# SCH_Amiga-KickSmash-32-in-system-flash_2.net
KiCad netlist of a schematic drawn in EasyEDA
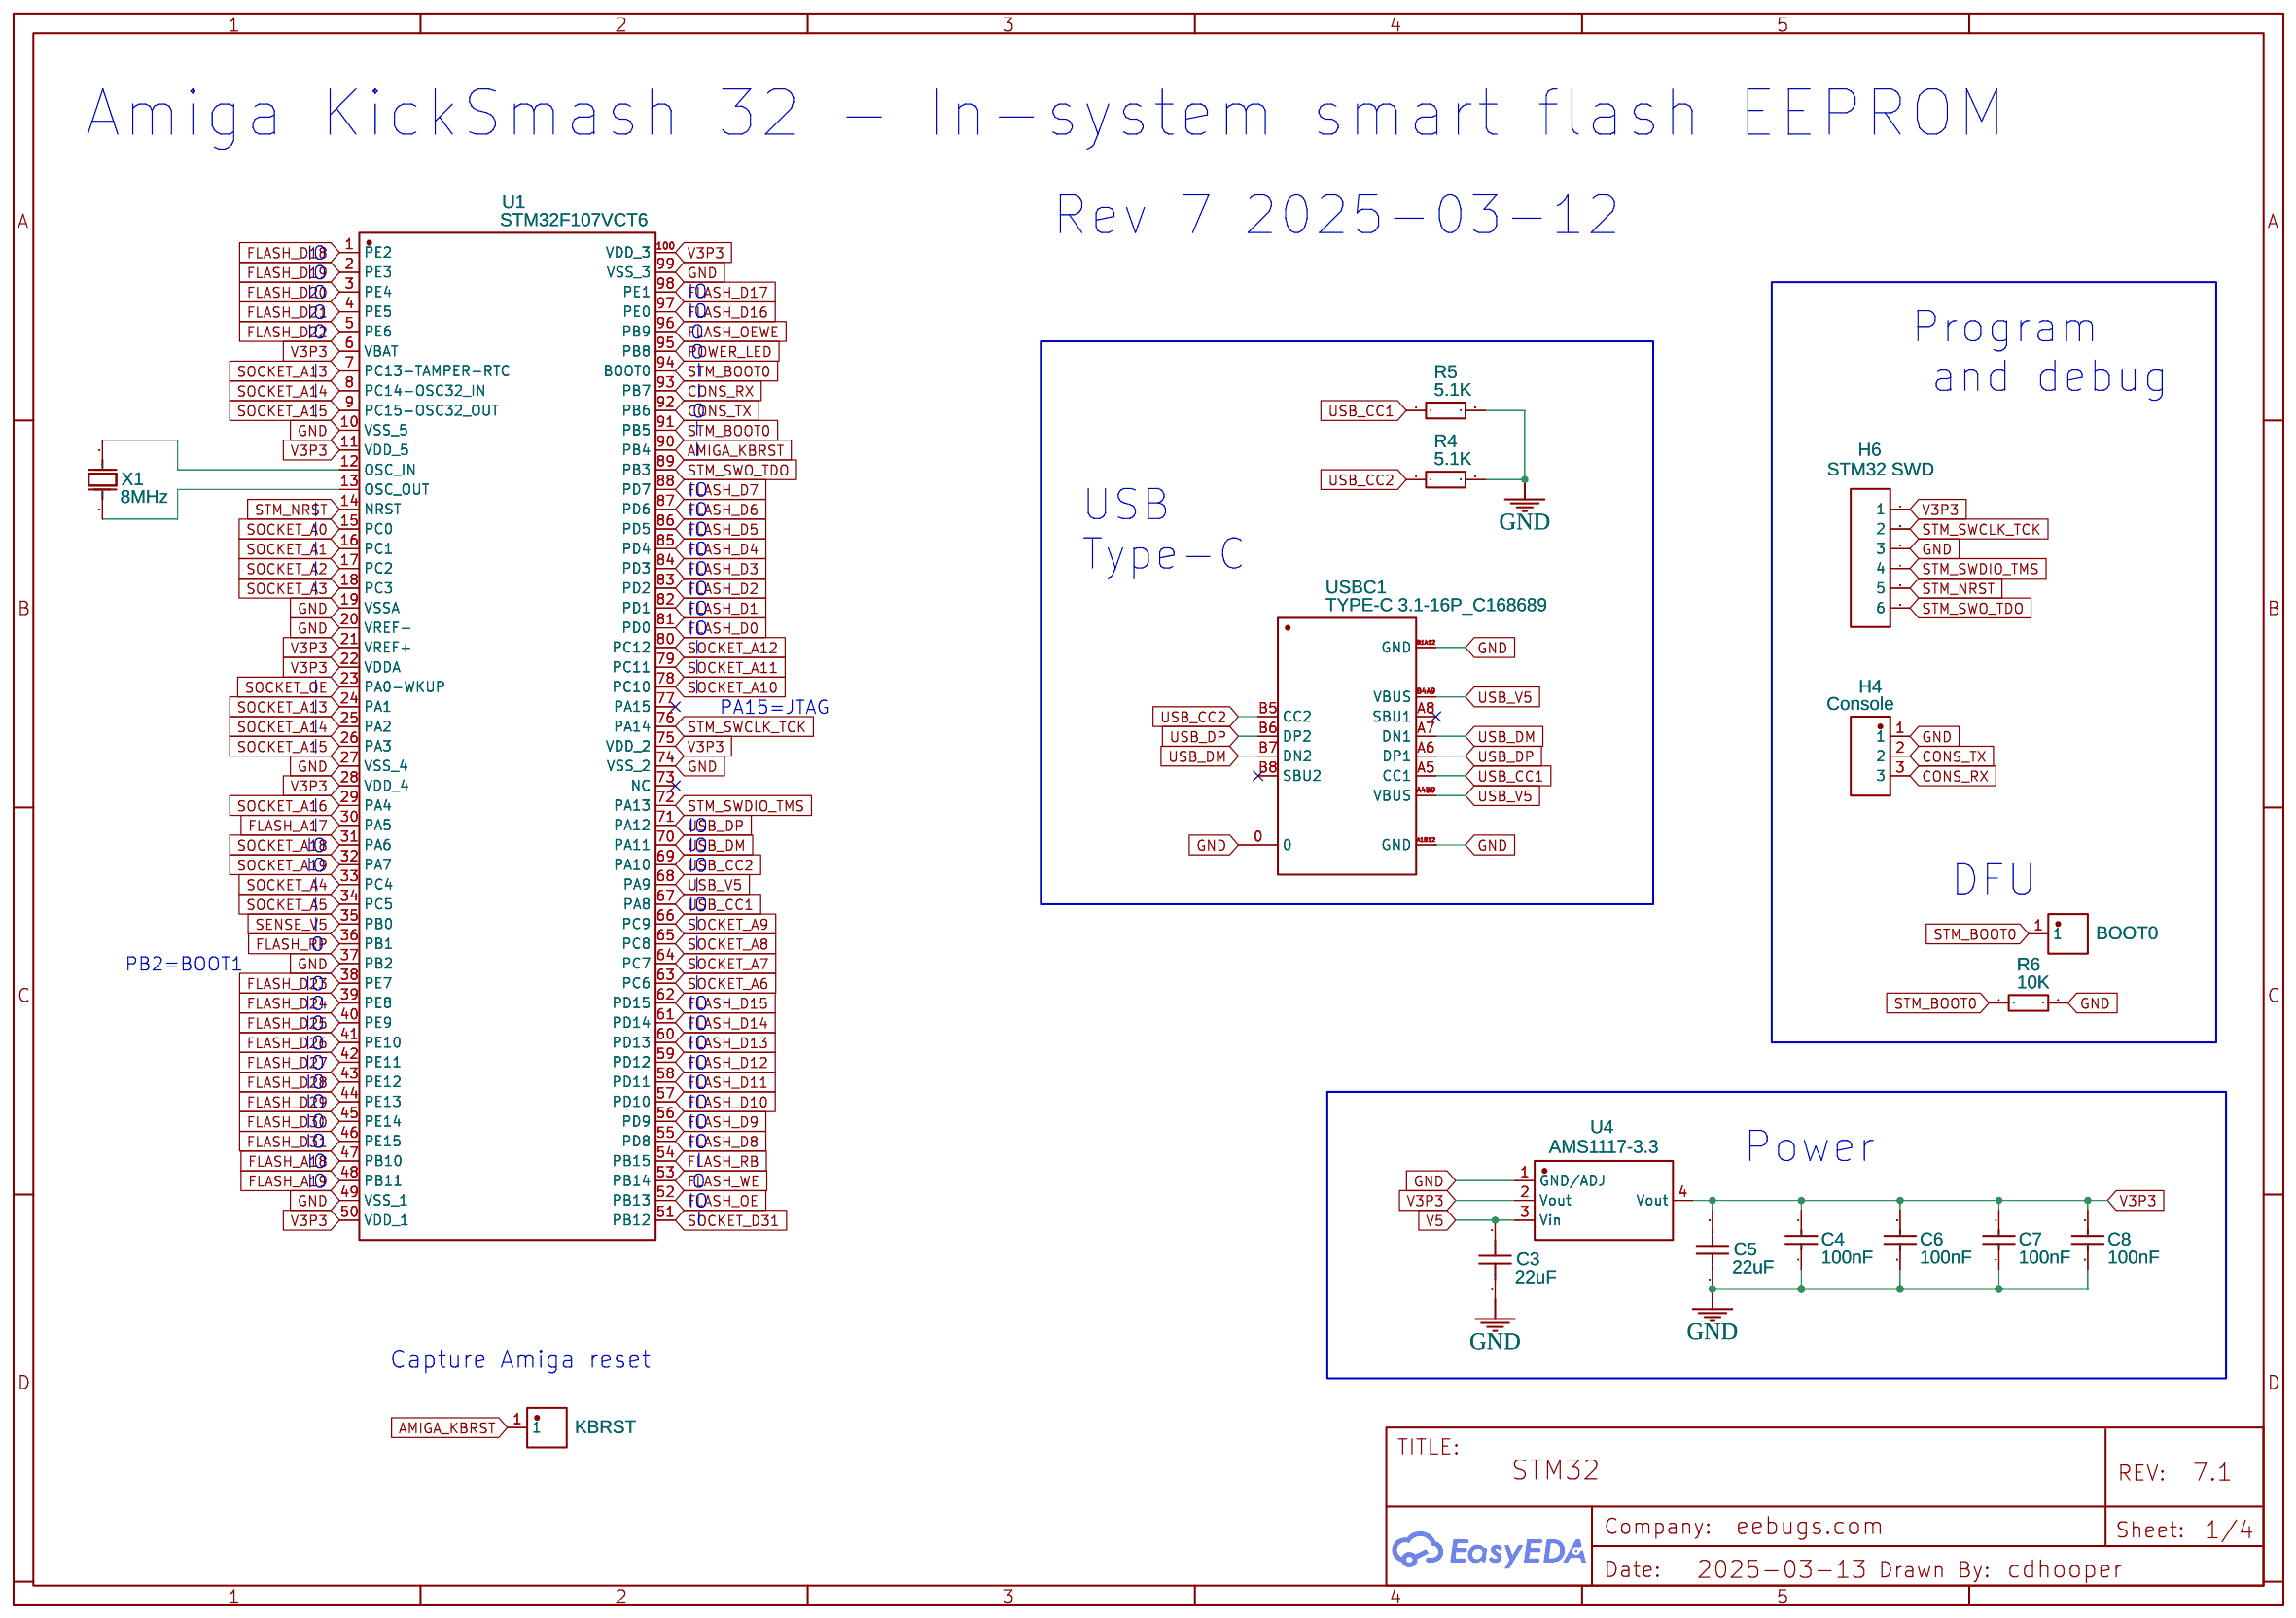
[diagram p0: STM32]
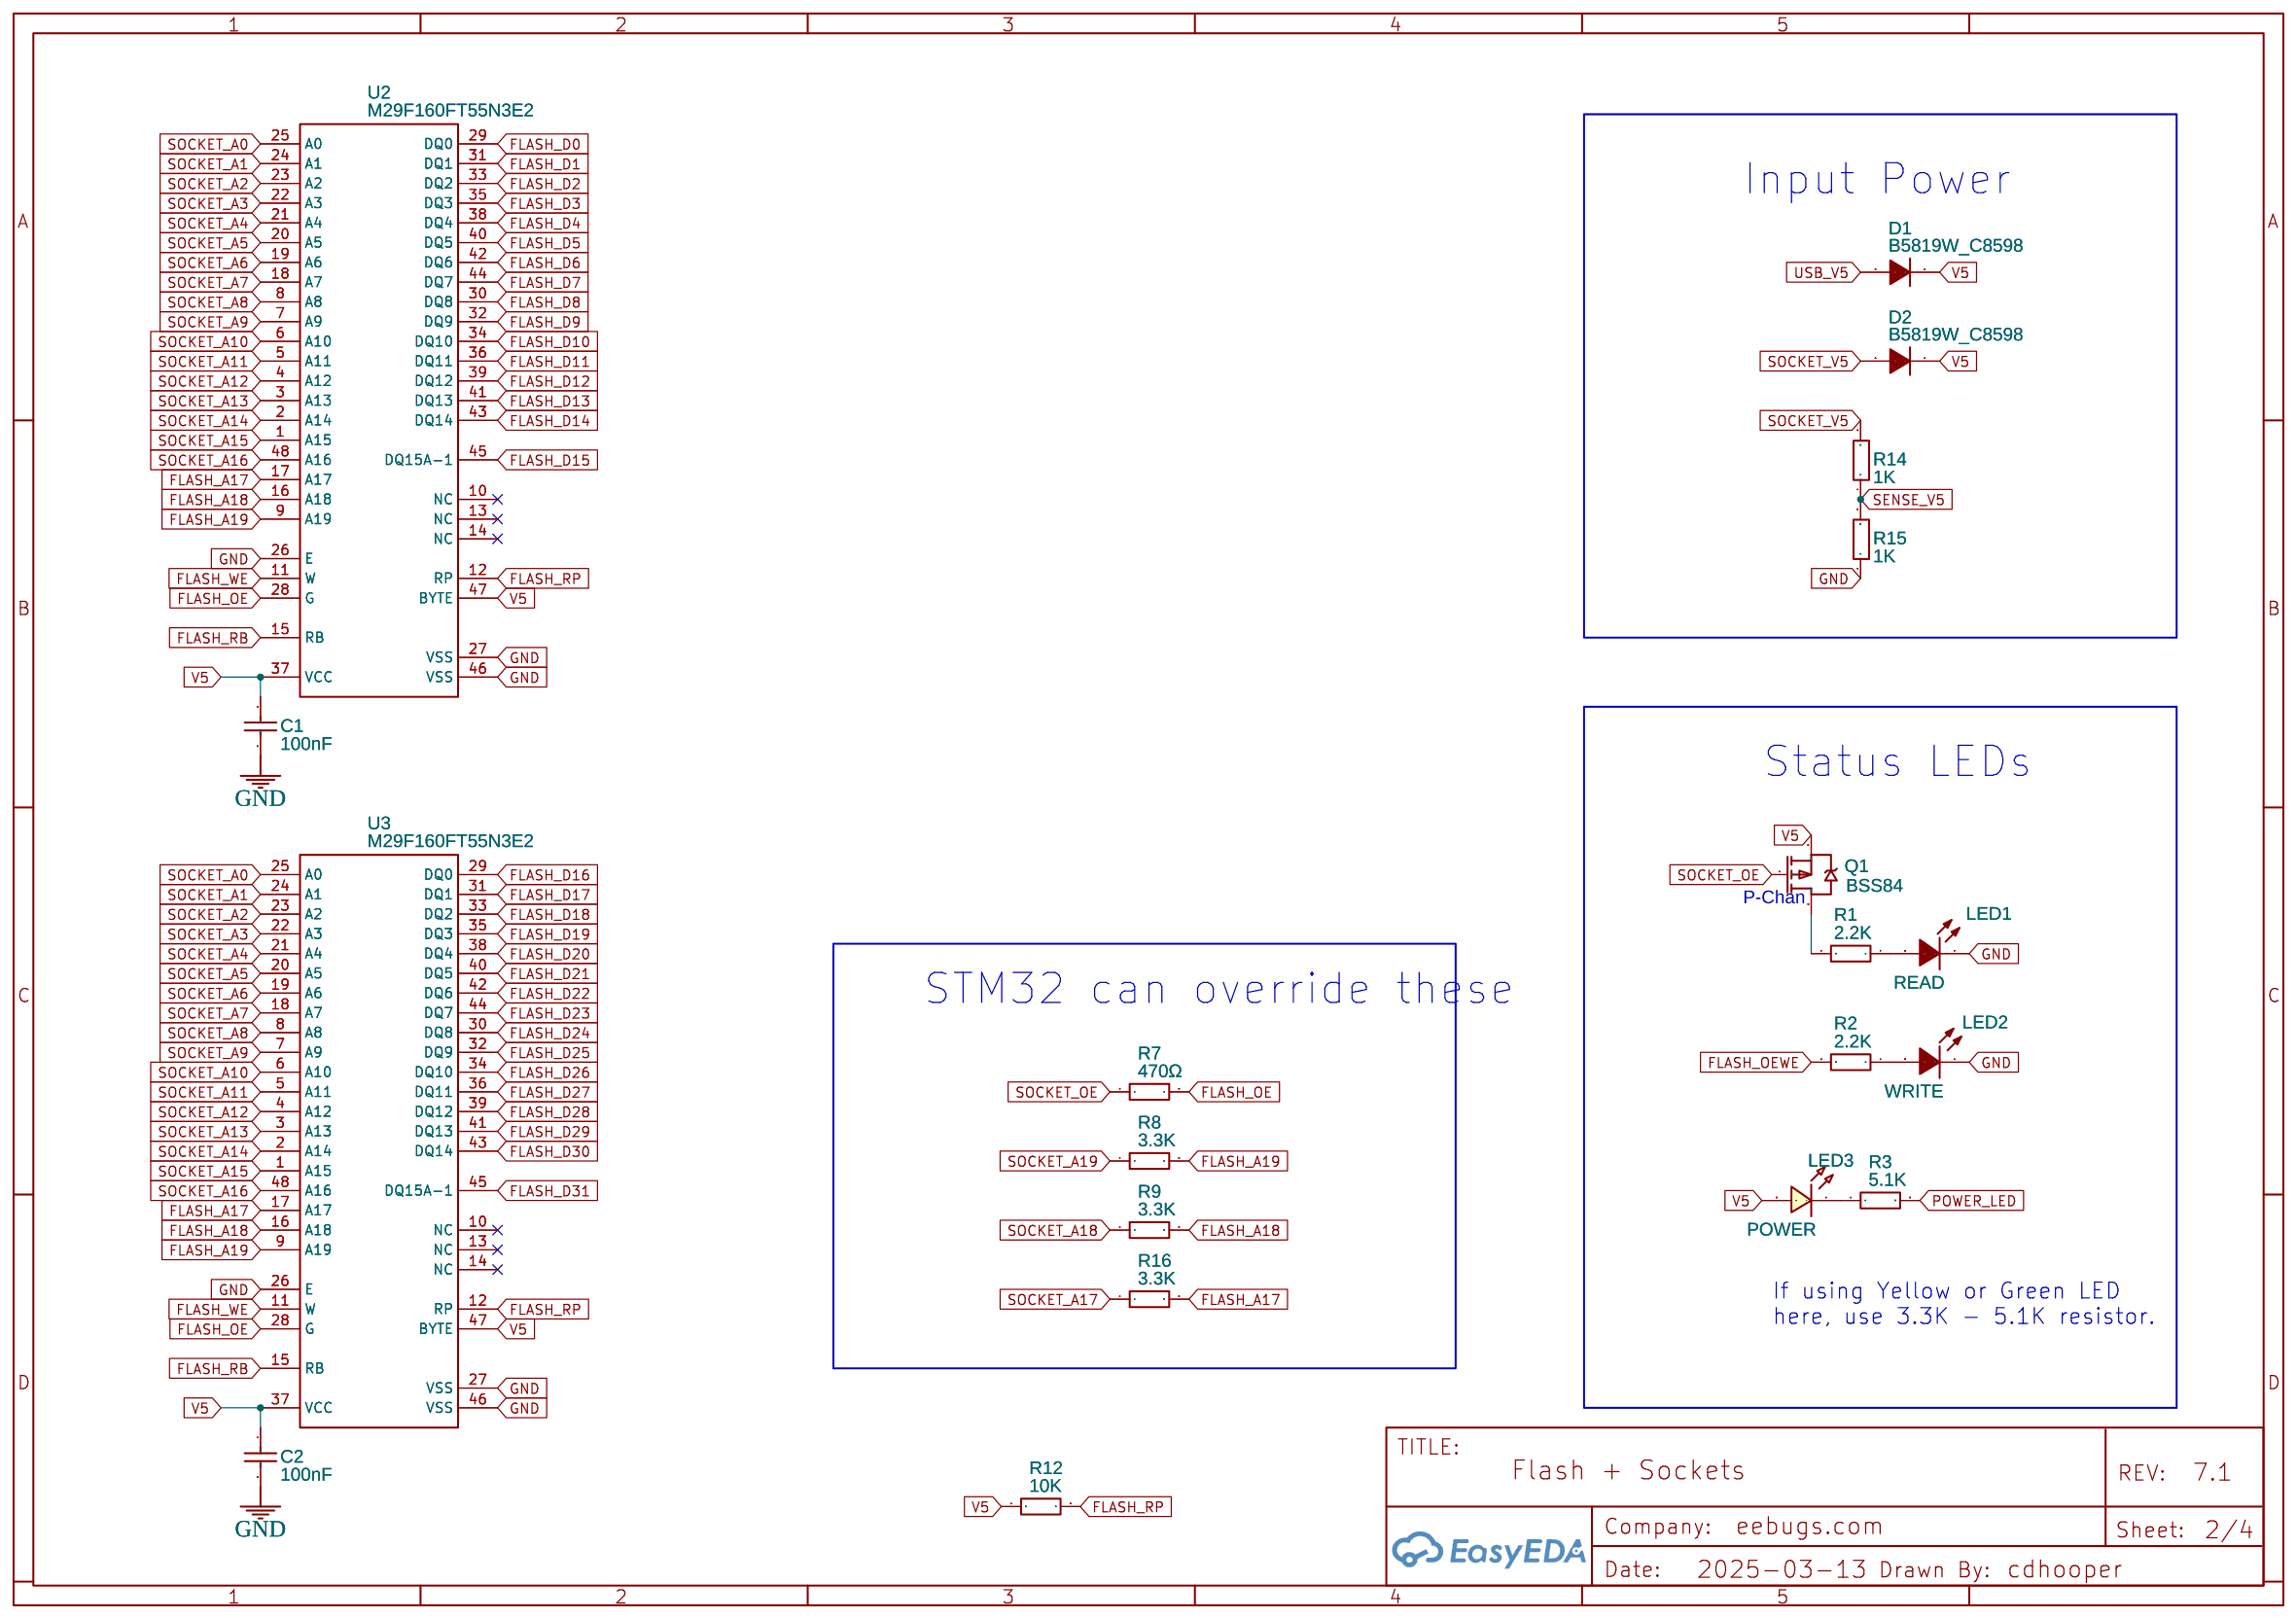
[diagram p1: Flash]
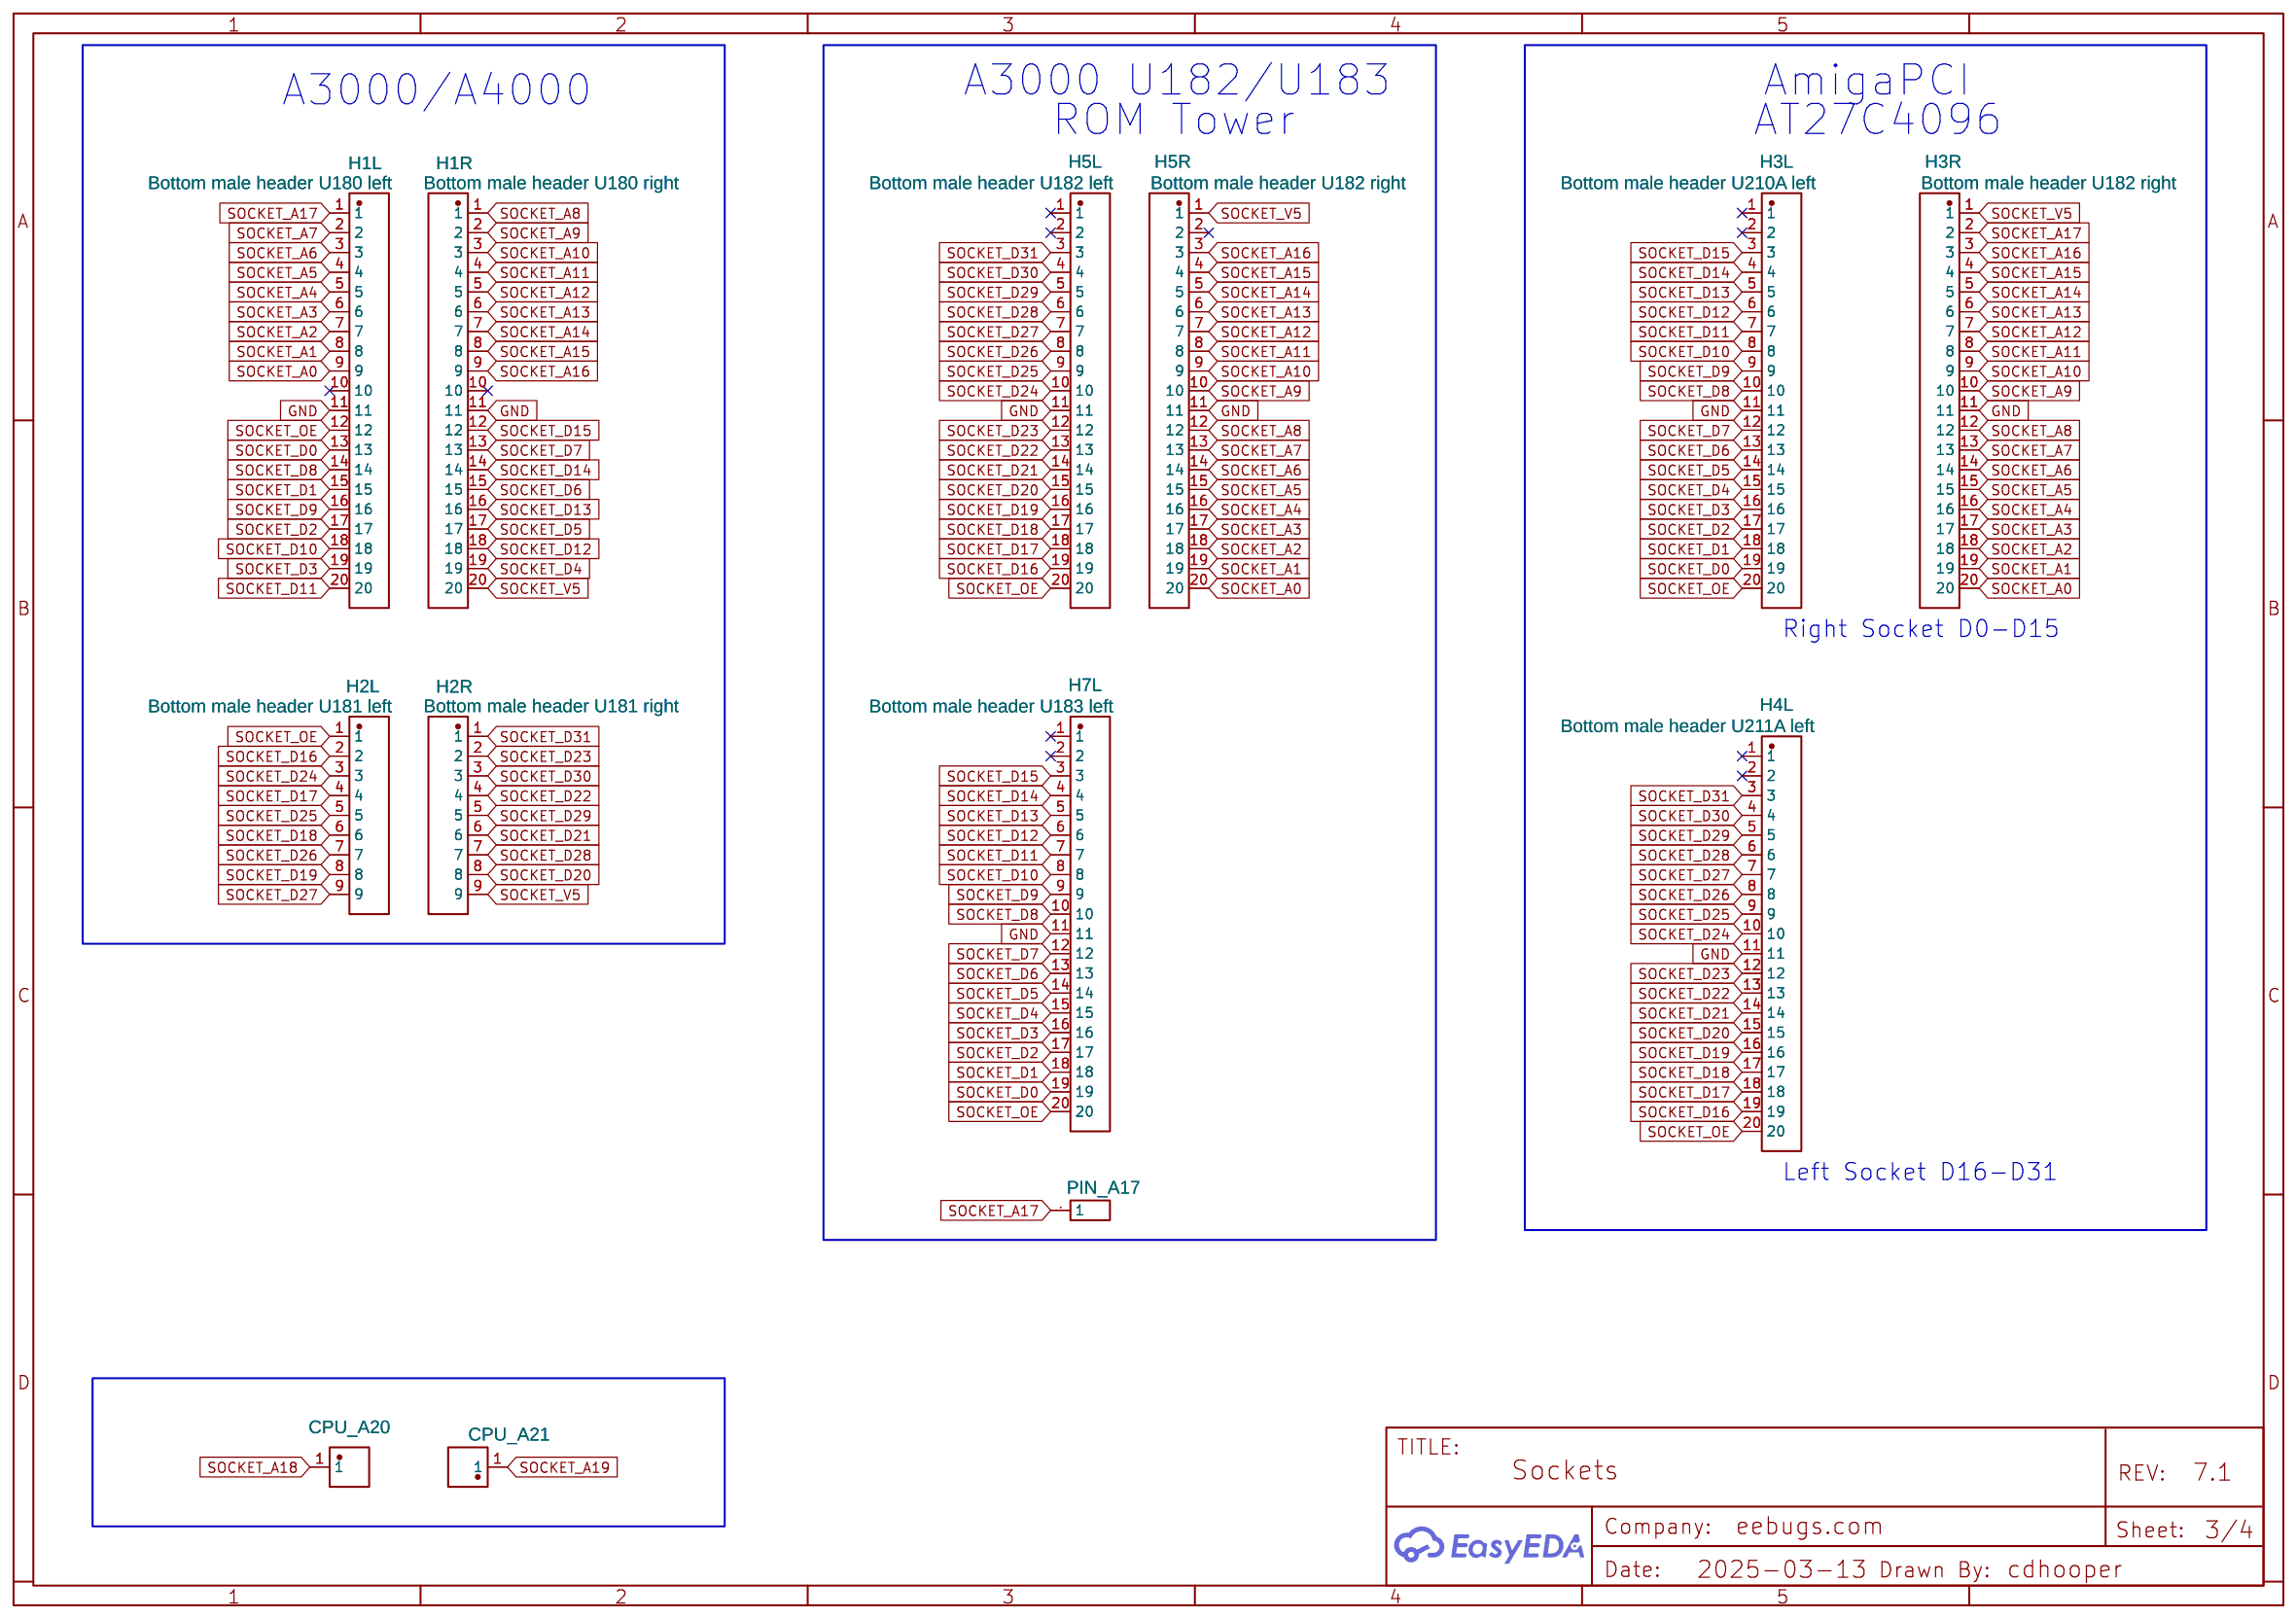
[diagram p2: Sockets]
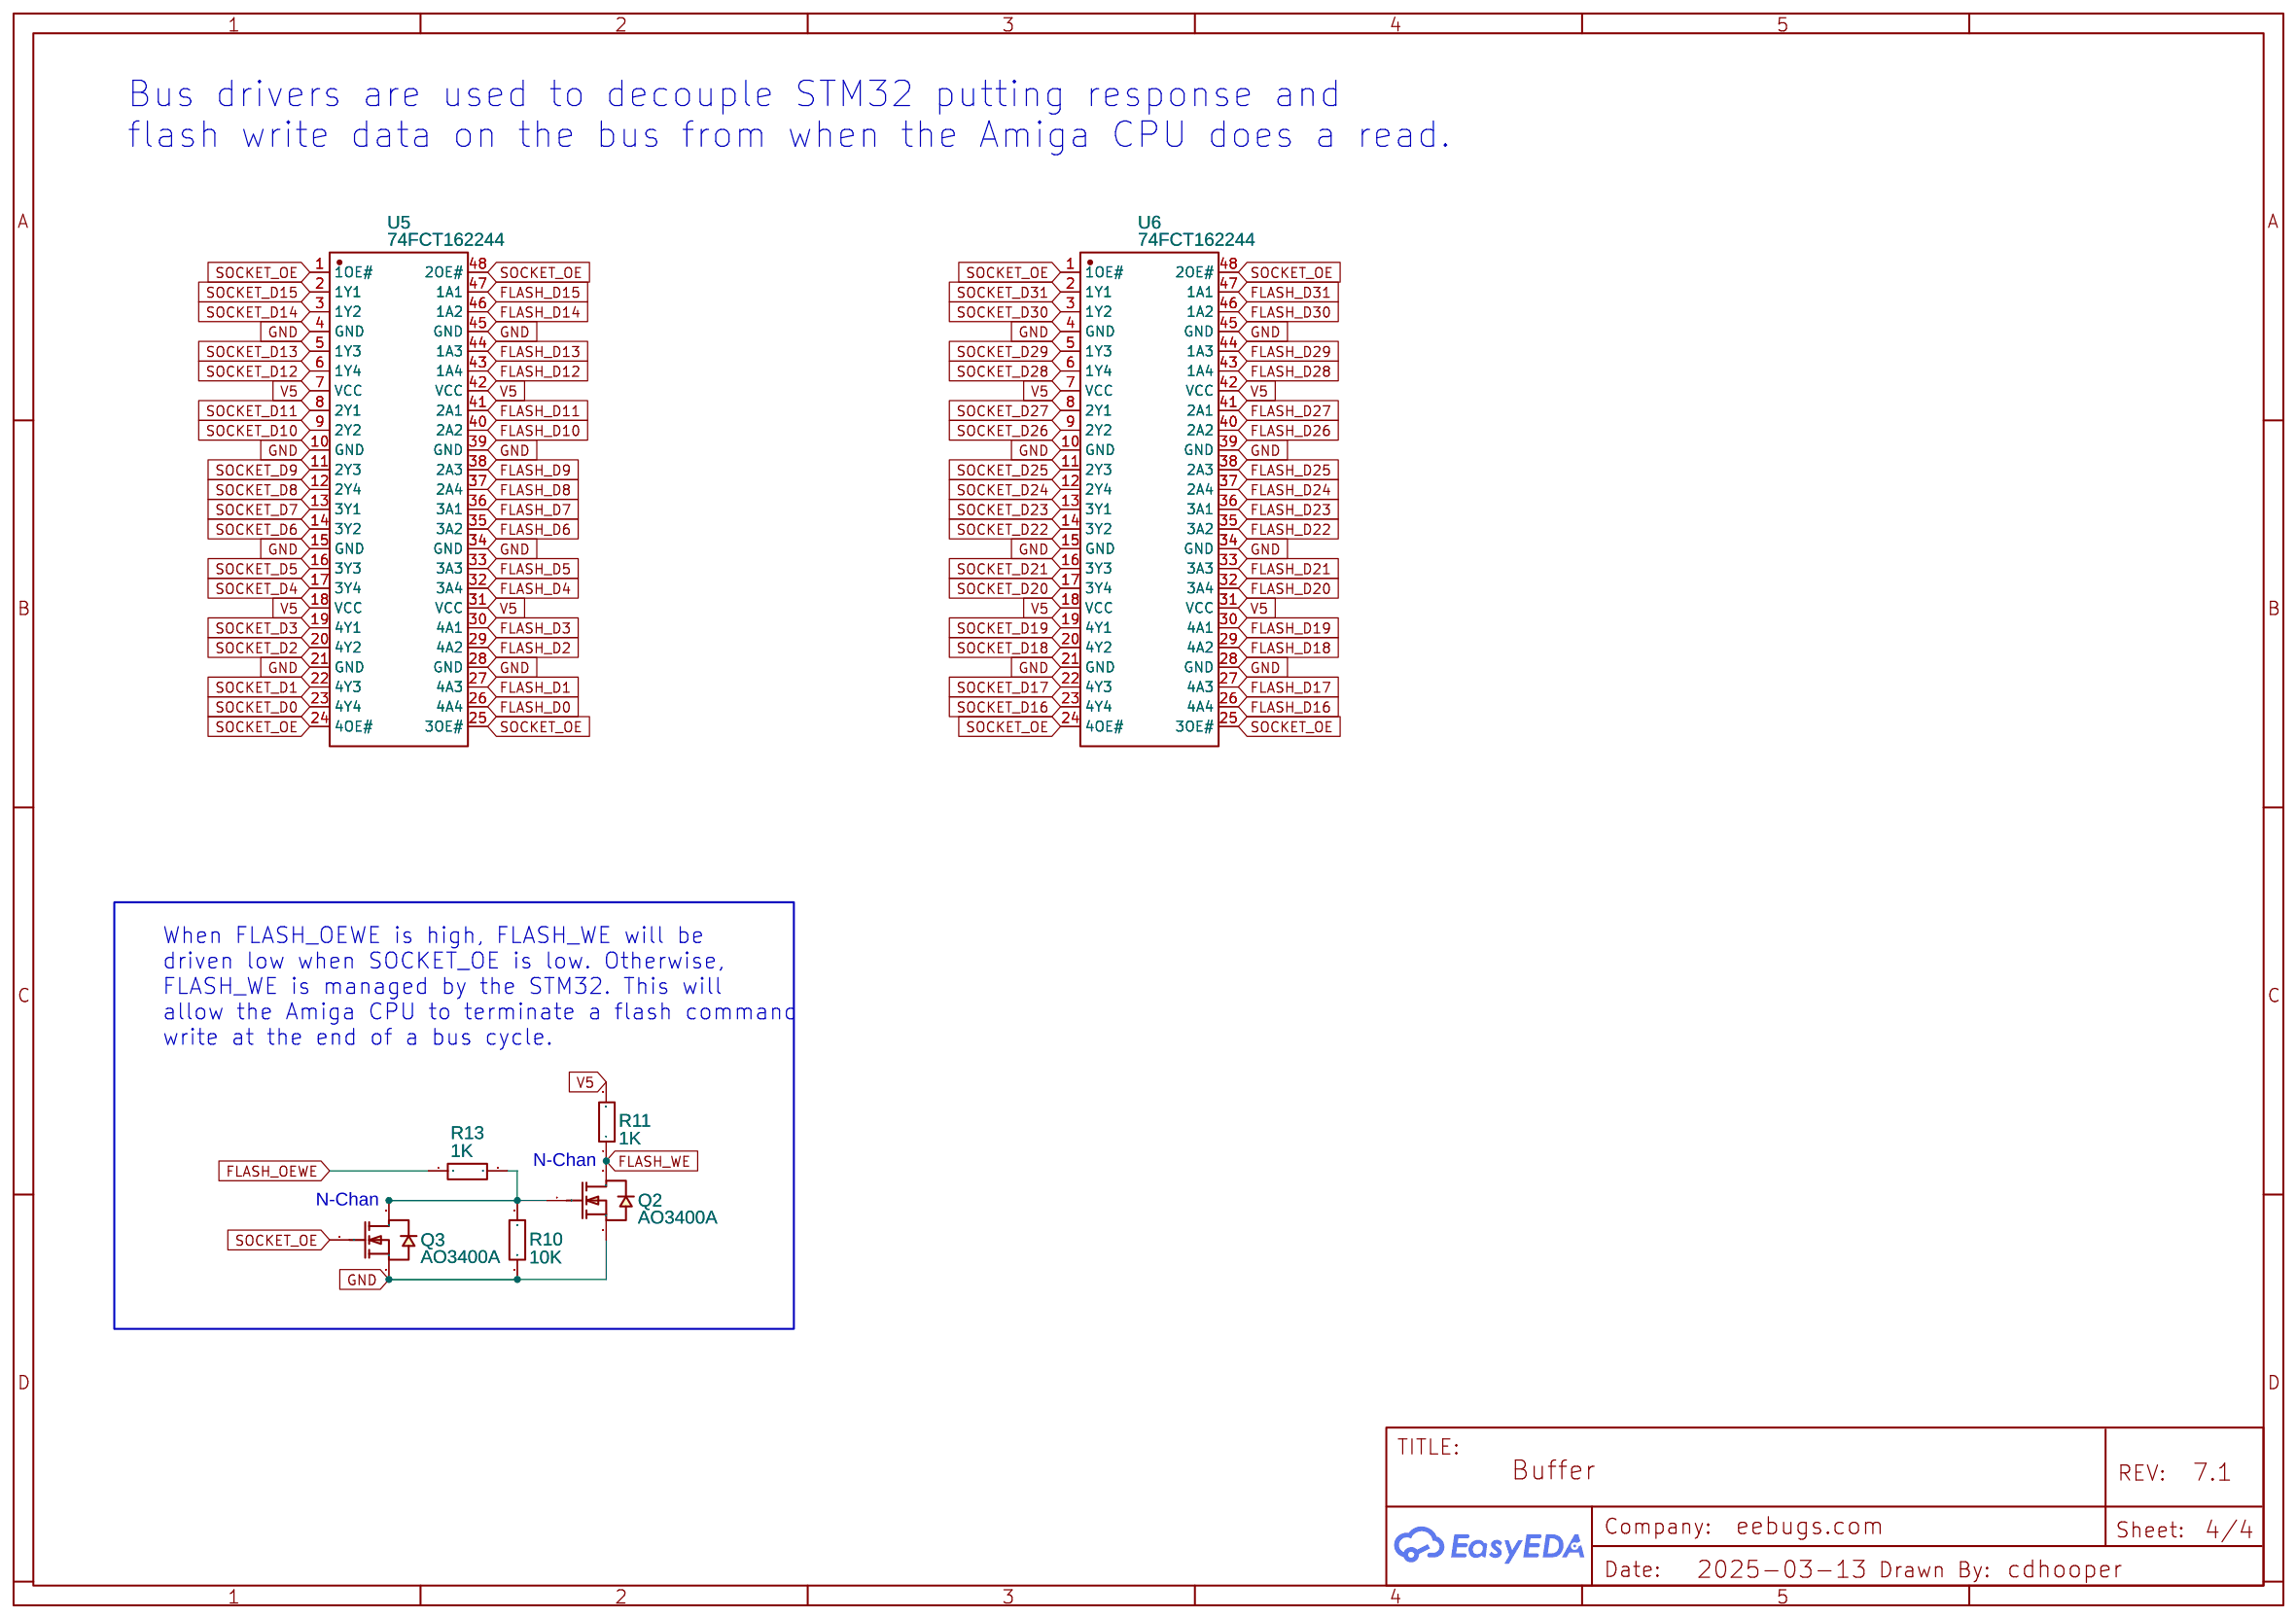
[diagram p3: Buffer]

(export (version "E")
  (design (tool "Eeschema 10.0.6"))
  (components
    (comp (ref "C3")
      (value "22uF")
      (fields (field (name "Manufacturer Part") "CL21A226MAQNNNE") (field (name "Manufacturer") "SAMSUNG"))
      (libsource (lib "") (part "CL21A226MAQNNNE"))
    )
    (comp (ref "C4")
      (value "100nF")
      (fields (field (name "Manufacturer Part") "CC0805KRX7R9BB104") (field (name "Manufacturer") "YAGEO"))
      (libsource (lib "") (part "CC0805KRX7R9BB104"))
    )
    (comp (ref "C5")
      (value "22uF")
      (fields (field (name "Manufacturer Part") "CL21A226MAQNNNE") (field (name "Manufacturer") "SAMSUNG"))
      (libsource (lib "") (part "CL21A226MAQNNNE"))
    )
    (comp (ref "C6")
      (value "100nF")
      (fields (field (name "Manufacturer Part") "CC0805KRX7R9BB104") (field (name "Manufacturer") "YAGEO"))
      (libsource (lib "") (part "CC0805KRX7R9BB104"))
    )
    (comp (ref "C7")
      (value "100nF")
      (fields (field (name "Manufacturer Part") "CC0805KRX7R9BB104") (field (name "Manufacturer") "YAGEO"))
      (libsource (lib "") (part "CC0805KRX7R9BB104"))
    )
    (comp (ref "C8")
      (value "100nF")
      (fields (field (name "Manufacturer Part") "CC0805KRX7R9BB104") (field (name "Manufacturer") "YAGEO"))
      (libsource (lib "") (part "CC0805KRX7R9BB104"))
    )
    (comp (ref "H3")
      (value "KBRST")
      (fields
        (field (name "Manufacturer Part") "X6511WR-01H-C60D30R2")
        (field (name "Manufacturer") "XKB Connection(中国星坤)")
      )
      (libsource (lib "") (part "X6511WR-01H-C30D60R2"))
    )
    (comp (ref "H4")
      (value "Console")
      (fields (field (name "Manufacturer Part") "PZ254R-11-03P") (field (name "Manufacturer") "XFCN(兴飞)"))
      (libsource (lib "") (part "PZ254R-11-03P"))
    )
    (comp (ref "H5")
      (value "BOOT0")
      (fields
        (field (name "Manufacturer Part") "X6511WR-01H-C60D30R2")
        (field (name "Manufacturer") "XKB Connection(中国星坤)")
      )
      (libsource (lib "") (part "X6511WR-01H-C30D60R2"))
    )
    (comp (ref "H6")
      (value "STM32 SWD")
      (fields (field (name "Manufacturer Part") "Female header 1*6p") (field (name "Manufacturer") "BOOMELE"))
      (libsource (lib "") (part "Unknown_945_-530"))
    )
    (comp (ref "R4")
      (value "5.1K")
      (fields (field (name "Manufacturer Part") "0805W8F5101T5E") (field (name "Manufacturer") "UniOhm"))
      (libsource (lib "") (part "0805W8F5101T5E"))
    )
    (comp (ref "R5")
      (value "5.1K")
      (fields (field (name "Manufacturer Part") "0805W8F5101T5E") (field (name "Manufacturer") "UniOhm"))
      (libsource (lib "") (part "0805W8F5101T5E"))
    )
    (comp (ref "R6")
      (value "10K")
      (fields (field (name "Manufacturer Part") "0805W8F1002T5E") (field (name "Manufacturer") "UniOhm"))
      (libsource (lib "") (part "0805W8F1002T5E"))
    )
    (comp (ref "U1")
      (value "STM32F107VCT6")
      (fields (field (name "Manufacturer") "STMicroelectronics"))
      (libsource (lib "") (part "STM32F107VCT6"))
    )
    (comp (ref "U4")
      (value "AMS1117-3.3")
      (fields (field (name "Manufacturer") "AMS"))
      (libsource (lib "") (part "AMS1117-3.3"))
    )
    (comp (ref "USBC1")
      (value "TYPE-C 3.1-16P_C168689")
      (fields (field (name "Manufacturer") "LCSC"))
      (libsource (lib "") (part "TYPE-C 3.1-16P_C168689"))
    )
    (comp (ref "X1")
      (value "8MHz")
      (fields (field (name "Manufacturer Part") "X50328MSB2GI") (field (name "Manufacturer") "YXC"))
      (libsource (lib "") (part "X50328MSB2GI"))
    )
    (comp (ref "C1")
      (value "100nF")
      (fields (field (name "Manufacturer Part") "CC0805KRX7R9BB104") (field (name "Manufacturer") "YAGEO"))
      (libsource (lib "") (part "CC0805KRX7R9BB104"))
    )
    (comp (ref "C2")
      (value "100nF")
      (fields (field (name "Manufacturer Part") "CC0805KRX7R9BB104") (field (name "Manufacturer") "YAGEO"))
      (libsource (lib "") (part "CC0805KRX7R9BB104"))
    )
    (comp (ref "D1")
      (value "B5819W_C8598")
      (fields (field (name "Manufacturer Part") "B5819W") (field (name "Manufacturer") "CJ"))
      (libsource (lib "") (part "B5819W_C8598"))
    )
    (comp (ref "D2")
      (value "B5819W_C8598")
      (fields (field (name "Manufacturer Part") "B5819W") (field (name "Manufacturer") "CJ"))
      (libsource (lib "") (part "B5819W_C8598"))
    )
    (comp (ref "LED1")
      (value "READ")
      (fields (field (name "Manufacturer Part") "17-21SUYC/TR8") (field (name "Manufacturer") "KENTO"))
      (libsource (lib "") (part "17-21SUYC/TR8"))
    )
    (comp (ref "LED2")
      (value "WRITE")
      (fields (field (name "Manufacturer Part") "0805G (Green)") (field (name "Manufacturer") "KENTO"))
      (libsource (lib "") (part "0805G (Green)"))
    )
    (comp (ref "LED3")
      (value "POWER")
      (fields
        (field (name "Manufacturer Part") "P2-0805UVTCS2-0.8T")
        (field (name "Manufacturer") "TUOZHAN(拓展光电)")
      )
      (libsource (lib "") (part "P2-0805UVTCS2-0.8T"))
    )
    (comp (ref "Q1")
      (value "BSS84")
      (fields (field (name "Manufacturer Part") "LBSS84LT1G") (field (name "Manufacturer") "LRC"))
      (libsource (lib "") (part "Unknown_905_-370"))
    )
    (comp (ref "R1")
      (value "2.2K")
      (fields (field (name "Manufacturer Part") "0805W8F2201T5E") (field (name "Manufacturer") "UniOhm"))
      (libsource (lib "") (part "0805W8F2201T5E"))
    )
    (comp (ref "R2")
      (value "2.2K")
      (fields (field (name "Manufacturer Part") "0805W8F2201T5E") (field (name "Manufacturer") "UniOhm"))
      (libsource (lib "") (part "0805W8F2201T5E"))
    )
    (comp (ref "R3")
      (value "5.1K")
      (fields (field (name "Manufacturer Part") "0805W8F5101T5E") (field (name "Manufacturer") "UniOhm"))
      (libsource (lib "") (part "0805W8F5101T5E"))
    )
    (comp (ref "R7")
      (value "470Ω")
      (fields
        (field (name "Manufacturer Part") "0805W8F4700T5E")
        (field (name "Manufacturer") "UNI-ROYAL(厚声)")
      )
      (libsource (lib "") (part "0805W8F4700T5E"))
    )
    (comp (ref "R8")
      (value "3.3K")
      (fields
        (field (name "Manufacturer Part") "0805W8F3301T5E")
        (field (name "Manufacturer") "UNI-ROYAL(厚声)")
      )
      (libsource (lib "") (part "0805W8F3301T5E"))
    )
    (comp (ref "R9")
      (value "3.3K")
      (fields
        (field (name "Manufacturer Part") "0805W8F3301T5E")
        (field (name "Manufacturer") "UNI-ROYAL(厚声)")
      )
      (libsource (lib "") (part "0805W8F3301T5E"))
    )
    (comp (ref "R12")
      (value "10K")
      (fields (field (name "Manufacturer Part") "0805W8F1002T5E") (field (name "Manufacturer") "UniOhm"))
      (libsource (lib "") (part "0805W8F1002T5E"))
    )
    (comp (ref "R14")
      (value "1K")
      (fields (field (name "Manufacturer Part") "0805W8F1001T5E") (field (name "Manufacturer") "UniOhm"))
      (libsource (lib "") (part "0805W8F1001T5E"))
    )
    (comp (ref "R15")
      (value "1K")
      (fields (field (name "Manufacturer Part") "0805W8F1001T5E") (field (name "Manufacturer") "UniOhm"))
      (libsource (lib "") (part "0805W8F1001T5E"))
    )
    (comp (ref "R16")
      (value "3.3K")
      (fields
        (field (name "Manufacturer Part") "0805W8F3301T5E")
        (field (name "Manufacturer") "UNI-ROYAL(厚声)")
      )
      (libsource (lib "") (part "0805W8F3301T5E"))
    )
    (comp (ref "U2") (value "M29F160FT55N3E2") (libsource (lib "") (part "M29F160FT55N3E2")))
    (comp (ref "U3") (value "M29F160FT55N3E2") (libsource (lib "") (part "M29F160FT55N3E2")))
    (comp (ref "H1L")
      (value "Bottom male header U180 left")
      (fields (field (name "Manufacturer Part") "PZ254-1-20-Z-C") (field (name "Manufacturer") "HCTL(华灿天禄)"))
      (libsource (lib "") (part "PZ254-1-20-Z-C"))
    )
    (comp (ref "H1R")
      (value "Bottom male header U180 right")
      (fields (field (name "Manufacturer Part") "PZ254-1-20-Z-C") (field (name "Manufacturer") "HCTL(华灿天禄)"))
      (libsource (lib "") (part "PZ254-1-20-Z-C_1"))
    )
    (comp (ref "H2L")
      (value "Bottom male header U181 left")
      (fields (field (name "Manufacturer Part") "PZ254-1-09-Z-C") (field (name "Manufacturer") "HCTL(华灿天禄)"))
      (libsource (lib "") (part "PZ254-1-09-Z-C_1"))
    )
    (comp (ref "H2R")
      (value "Bottom male header U181 right")
      (fields (field (name "Manufacturer Part") "PZ254-1-09-Z-C") (field (name "Manufacturer") "HCTL(华灿天禄)"))
      (libsource (lib "") (part "PZ254-1-09-Z-C"))
    )
    (comp (ref "H3L")
      (value "Bottom male header U210A left")
      (fields (field (name "Manufacturer Part") "2.54mm 1*20PHeader") (field (name "Manufacturer") "BOOMELE"))
      (libsource (lib "") (part "Header-Male-2.54_1x20_3"))
    )
    (comp (ref "H3R")
      (value "Bottom male header U182 right")
      (fields (field (name "Manufacturer Part") "2.54mm 1*20PHeader") (field (name "Manufacturer") "BOOMELE"))
      (libsource (lib "") (part "Header-Male-2.54_1x20_2"))
    )
    (comp (ref "H4L")
      (value "Bottom male header U211A left")
      (fields (field (name "Manufacturer Part") "2.54mm 1*20PHeader") (field (name "Manufacturer") "BOOMELE"))
      (libsource (lib "") (part "Header-Male-2.54_1x20_5"))
    )
    (comp (ref "H5L")
      (value "Bottom male header U182 left")
      (fields (field (name "Manufacturer Part") "2.54mm 1*20PHeader") (field (name "Manufacturer") "BOOMELE"))
      (libsource (lib "") (part "Header-Male-2.54_1x20_1"))
    )
    (comp (ref "H5R")
      (value "Bottom male header U182 right")
      (fields (field (name "Manufacturer Part") "2.54mm 1*20PHeader") (field (name "Manufacturer") "BOOMELE"))
      (libsource (lib "") (part "Header-Male-2.54_1x20"))
    )
    (comp (ref "H7")
      (value "CPU_A20")
      (fields
        (field (name "Manufacturer Part") "X6511WR-01H-C60D30R2")
        (field (name "Manufacturer") "XKB Connection(中国星坤)")
      )
      (libsource (lib "") (part "X6511WR-01H-C30D60R2_1"))
    )
    (comp (ref "H7L")
      (value "Bottom male header U183 left")
      (fields (field (name "Manufacturer Part") "2.54mm 1*20PHeader") (field (name "Manufacturer") "BOOMELE"))
      (libsource (lib "") (part "Header-Male-2.54_1x20_4"))
    )
    (comp (ref "H8")
      (value "CPU_A21")
      (fields
        (field (name "Manufacturer Part") "X6511WR-01H-C60D30R2")
        (field (name "Manufacturer") "XKB Connection(中国星坤)")
      )
      (libsource (lib "") (part "X6511WR-01H-C30D60R2"))
    )
    (comp (ref "H9")
      (value "PIN_A17")
      (fields
        (field (name "Manufacturer Part") "Header-Male-2.54_1x1")
        (field (name "Manufacturer") "ReliaPro")
      )
      (libsource (lib "") (part "Header-Male-2.54_1x1"))
    )
    (comp (ref "Q2")
      (value "AO3400A")
      (fields (field (name "Manufacturer") "AOS"))
      (libsource (lib "") (part "AO3400A"))
    )
    (comp (ref "Q3")
      (value "AO3400A")
      (fields (field (name "Manufacturer") "AOS"))
      (libsource (lib "") (part "AO3400A"))
    )
    (comp (ref "R10")
      (value "10K")
      (fields (field (name "Manufacturer Part") "0805W8F1002T5E") (field (name "Manufacturer") "UniOhm"))
      (libsource (lib "") (part "0805W8F1002T5E"))
    )
    (comp (ref "R11")
      (value "1K")
      (fields (field (name "Manufacturer Part") "0805W8F1001T5E") (field (name "Manufacturer") "UniOhm"))
      (libsource (lib "") (part "0805W8F1001T5E"))
    )
    (comp (ref "R13")
      (value "1K")
      (fields (field (name "Manufacturer Part") "0805W8F1001T5E") (field (name "Manufacturer") "UniOhm"))
      (libsource (lib "") (part "0805W8F1001T5E_1"))
    )
    (comp (ref "U5")
      (value "74FCT162244")
      (fields
        (field (name "Manufacturer Part") "74FCT162244CTPAG")
        (field (name "Manufacturer") "RENESAS(瑞萨)/IDT")
      )
      (libsource (lib "") (part "74FCT162244CTPAG"))
    )
    (comp (ref "U6")
      (value "74FCT162244")
      (fields
        (field (name "Manufacturer Part") "74FCT162244CTPAG")
        (field (name "Manufacturer") "RENESAS(瑞萨)/IDT")
      )
      (libsource (lib "") (part "74FCT162244CTPAG"))
    )
  )
  (nets
    (net (code "1") (name "AMIGA_KBRST") (class "Default")
      (node (ref "H3") (pin "1") (pinfunction "1_1") (pintype "unspecified"))
      (node (ref "U1") (pin "90") (pinfunction "PB4_90") (pintype "unspecified"))
    )
    (net (code "2") (name "CONS_RX") (class "Default")
      (node (ref "H4") (pin "3") (pinfunction "3_3") (pintype "unspecified"))
      (node (ref "U1") (pin "93") (pinfunction "PB7_93") (pintype "unspecified"))
    )
    (net (code "3") (name "CONS_TX") (class "Default")
      (node (ref "H4") (pin "2") (pinfunction "2_2") (pintype "unspecified"))
      (node (ref "U1") (pin "92") (pinfunction "PB6_92") (pintype "unspecified"))
    )
    (net (code "4") (name "FLASH_A17") (class "Default")
      (node (ref "R16") (pin "2") (pinfunction "2_2") (pintype "input"))
      (node (ref "U1") (pin "30") (pinfunction "PA5_30") (pintype "unspecified"))
      (node (ref "U2") (pin "17") (pinfunction "A17_17") (pintype "unspecified"))
      (node (ref "U3") (pin "17") (pinfunction "A17_17") (pintype "unspecified"))
    )
    (net (code "5") (name "FLASH_A18") (class "Default")
      (node (ref "R9") (pin "2") (pinfunction "2_2") (pintype "input"))
      (node (ref "U1") (pin "47") (pinfunction "PB10_47") (pintype "unspecified"))
      (node (ref "U2") (pin "16") (pinfunction "A18_16") (pintype "unspecified"))
      (node (ref "U3") (pin "16") (pinfunction "A18_16") (pintype "unspecified"))
    )
    (net (code "6") (name "FLASH_A19") (class "Default")
      (node (ref "R8") (pin "2") (pinfunction "2_2") (pintype "input"))
      (node (ref "U1") (pin "48") (pinfunction "PB11_48") (pintype "unspecified"))
      (node (ref "U2") (pin "9") (pinfunction "A19_9") (pintype "unspecified"))
      (node (ref "U3") (pin "9") (pinfunction "A19_9") (pintype "unspecified"))
    )
    (net (code "7") (name "FLASH_D0") (class "Default")
      (node (ref "U1") (pin "81") (pinfunction "PD0_81") (pintype "unspecified"))
      (node (ref "U2") (pin "29") (pinfunction "DQ0_29") (pintype "bidirectional"))
      (node (ref "U5") (pin "26") (pinfunction "4A4_26") (pintype "unspecified"))
    )
    (net (code "8") (name "FLASH_D1") (class "Default")
      (node (ref "U1") (pin "82") (pinfunction "PD1_82") (pintype "unspecified"))
      (node (ref "U2") (pin "31") (pinfunction "DQ1_31") (pintype "bidirectional"))
      (node (ref "U5") (pin "27") (pinfunction "4A3_27") (pintype "unspecified"))
    )
    (net (code "9") (name "FLASH_D2") (class "Default")
      (node (ref "U1") (pin "83") (pinfunction "PD2_83") (pintype "unspecified"))
      (node (ref "U2") (pin "33") (pinfunction "DQ2_33") (pintype "bidirectional"))
      (node (ref "U5") (pin "29") (pinfunction "4A2_29") (pintype "unspecified"))
    )
    (net (code "10") (name "FLASH_D3") (class "Default")
      (node (ref "U1") (pin "84") (pinfunction "PD3_84") (pintype "unspecified"))
      (node (ref "U2") (pin "35") (pinfunction "DQ3_35") (pintype "bidirectional"))
      (node (ref "U5") (pin "30") (pinfunction "4A1_30") (pintype "unspecified"))
    )
    (net (code "11") (name "FLASH_D4") (class "Default")
      (node (ref "U1") (pin "85") (pinfunction "PD4_85") (pintype "unspecified"))
      (node (ref "U2") (pin "38") (pinfunction "DQ4_38") (pintype "bidirectional"))
      (node (ref "U5") (pin "32") (pinfunction "3A4_32") (pintype "unspecified"))
    )
    (net (code "12") (name "FLASH_D5") (class "Default")
      (node (ref "U1") (pin "86") (pinfunction "PD5_86") (pintype "unspecified"))
      (node (ref "U2") (pin "40") (pinfunction "DQ5_40") (pintype "bidirectional"))
      (node (ref "U5") (pin "33") (pinfunction "3A3_33") (pintype "unspecified"))
    )
    (net (code "13") (name "FLASH_D6") (class "Default")
      (node (ref "U1") (pin "87") (pinfunction "PD6_87") (pintype "unspecified"))
      (node (ref "U2") (pin "42") (pinfunction "DQ6_42") (pintype "bidirectional"))
      (node (ref "U5") (pin "35") (pinfunction "3A2_35") (pintype "unspecified"))
    )
    (net (code "14") (name "FLASH_D7") (class "Default")
      (node (ref "U1") (pin "88") (pinfunction "PD7_88") (pintype "unspecified"))
      (node (ref "U2") (pin "44") (pinfunction "DQ7_44") (pintype "bidirectional"))
      (node (ref "U5") (pin "36") (pinfunction "3A1_36") (pintype "unspecified"))
    )
    (net (code "15") (name "FLASH_D8") (class "Default")
      (node (ref "U1") (pin "55") (pinfunction "PD8_55") (pintype "unspecified"))
      (node (ref "U2") (pin "30") (pinfunction "DQ8_30") (pintype "bidirectional"))
      (node (ref "U5") (pin "37") (pinfunction "2A4_37") (pintype "unspecified"))
    )
    (net (code "16") (name "FLASH_D9") (class "Default")
      (node (ref "U1") (pin "56") (pinfunction "PD9_56") (pintype "unspecified"))
      (node (ref "U2") (pin "32") (pinfunction "DQ9_32") (pintype "bidirectional"))
      (node (ref "U5") (pin "38") (pinfunction "2A3_38") (pintype "unspecified"))
    )
    (net (code "17") (name "FLASH_D10") (class "Default")
      (node (ref "U1") (pin "57") (pinfunction "PD10_57") (pintype "unspecified"))
      (node (ref "U2") (pin "34") (pinfunction "DQ10_34") (pintype "bidirectional"))
      (node (ref "U5") (pin "40") (pinfunction "2A2_40") (pintype "unspecified"))
    )
    (net (code "18") (name "FLASH_D11") (class "Default")
      (node (ref "U1") (pin "58") (pinfunction "PD11_58") (pintype "unspecified"))
      (node (ref "U2") (pin "36") (pinfunction "DQ11_36") (pintype "bidirectional"))
      (node (ref "U5") (pin "41") (pinfunction "2A1_41") (pintype "unspecified"))
    )
    (net (code "19") (name "FLASH_D12") (class "Default")
      (node (ref "U1") (pin "59") (pinfunction "PD12_59") (pintype "unspecified"))
      (node (ref "U2") (pin "39") (pinfunction "DQ12_39") (pintype "bidirectional"))
      (node (ref "U5") (pin "43") (pinfunction "1A4_43") (pintype "unspecified"))
    )
    (net (code "20") (name "FLASH_D13") (class "Default")
      (node (ref "U1") (pin "60") (pinfunction "PD13_60") (pintype "unspecified"))
      (node (ref "U2") (pin "41") (pinfunction "DQ13_41") (pintype "bidirectional"))
      (node (ref "U5") (pin "44") (pinfunction "1A3_44") (pintype "unspecified"))
    )
    (net (code "21") (name "FLASH_D14") (class "Default")
      (node (ref "U1") (pin "61") (pinfunction "PD14_61") (pintype "unspecified"))
      (node (ref "U2") (pin "43") (pinfunction "DQ14_43") (pintype "bidirectional"))
      (node (ref "U5") (pin "46") (pinfunction "1A2_46") (pintype "unspecified"))
    )
    (net (code "22") (name "FLASH_D15") (class "Default")
      (node (ref "U1") (pin "62") (pinfunction "PD15_62") (pintype "unspecified"))
      (node (ref "U2") (pin "45") (pinfunction "DQ15A-1_45") (pintype "bidirectional"))
      (node (ref "U5") (pin "47") (pinfunction "1A1_47") (pintype "unspecified"))
    )
    (net (code "23") (name "FLASH_D16") (class "Default")
      (node (ref "U1") (pin "97") (pinfunction "PE0_97") (pintype "unspecified"))
      (node (ref "U3") (pin "29") (pinfunction "DQ0_29") (pintype "bidirectional"))
      (node (ref "U6") (pin "26") (pinfunction "4A4_26") (pintype "unspecified"))
    )
    (net (code "24") (name "FLASH_D17") (class "Default")
      (node (ref "U1") (pin "98") (pinfunction "PE1_98") (pintype "unspecified"))
      (node (ref "U3") (pin "31") (pinfunction "DQ1_31") (pintype "bidirectional"))
      (node (ref "U6") (pin "27") (pinfunction "4A3_27") (pintype "unspecified"))
    )
    (net (code "25") (name "FLASH_D18") (class "Default")
      (node (ref "U1") (pin "1") (pinfunction "PE2_1") (pintype "unspecified"))
      (node (ref "U3") (pin "33") (pinfunction "DQ2_33") (pintype "bidirectional"))
      (node (ref "U6") (pin "29") (pinfunction "4A2_29") (pintype "unspecified"))
    )
    (net (code "26") (name "FLASH_D19") (class "Default")
      (node (ref "U1") (pin "2") (pinfunction "PE3_2") (pintype "unspecified"))
      (node (ref "U3") (pin "35") (pinfunction "DQ3_35") (pintype "bidirectional"))
      (node (ref "U6") (pin "30") (pinfunction "4A1_30") (pintype "unspecified"))
    )
    (net (code "27") (name "FLASH_D20") (class "Default")
      (node (ref "U1") (pin "3") (pinfunction "PE4_3") (pintype "unspecified"))
      (node (ref "U3") (pin "38") (pinfunction "DQ4_38") (pintype "bidirectional"))
      (node (ref "U6") (pin "32") (pinfunction "3A4_32") (pintype "unspecified"))
    )
    (net (code "28") (name "FLASH_D21") (class "Default")
      (node (ref "U1") (pin "4") (pinfunction "PE5_4") (pintype "unspecified"))
      (node (ref "U3") (pin "40") (pinfunction "DQ5_40") (pintype "bidirectional"))
      (node (ref "U6") (pin "33") (pinfunction "3A3_33") (pintype "unspecified"))
    )
    (net (code "29") (name "FLASH_D22") (class "Default")
      (node (ref "U1") (pin "5") (pinfunction "PE6_5") (pintype "unspecified"))
      (node (ref "U3") (pin "42") (pinfunction "DQ6_42") (pintype "bidirectional"))
      (node (ref "U6") (pin "35") (pinfunction "3A2_35") (pintype "unspecified"))
    )
    (net (code "30") (name "FLASH_D23") (class "Default")
      (node (ref "U1") (pin "38") (pinfunction "PE7_38") (pintype "unspecified"))
      (node (ref "U3") (pin "44") (pinfunction "DQ7_44") (pintype "bidirectional"))
      (node (ref "U6") (pin "36") (pinfunction "3A1_36") (pintype "unspecified"))
    )
    (net (code "31") (name "FLASH_D24") (class "Default")
      (node (ref "U1") (pin "39") (pinfunction "PE8_39") (pintype "unspecified"))
      (node (ref "U3") (pin "30") (pinfunction "DQ8_30") (pintype "bidirectional"))
      (node (ref "U6") (pin "37") (pinfunction "2A4_37") (pintype "unspecified"))
    )
    (net (code "32") (name "FLASH_D25") (class "Default")
      (node (ref "U1") (pin "40") (pinfunction "PE9_40") (pintype "unspecified"))
      (node (ref "U3") (pin "32") (pinfunction "DQ9_32") (pintype "bidirectional"))
      (node (ref "U6") (pin "38") (pinfunction "2A3_38") (pintype "unspecified"))
    )
    (net (code "33") (name "FLASH_D26") (class "Default")
      (node (ref "U1") (pin "41") (pinfunction "PE10_41") (pintype "unspecified"))
      (node (ref "U3") (pin "34") (pinfunction "DQ10_34") (pintype "bidirectional"))
      (node (ref "U6") (pin "40") (pinfunction "2A2_40") (pintype "unspecified"))
    )
    (net (code "34") (name "FLASH_D27") (class "Default")
      (node (ref "U1") (pin "42") (pinfunction "PE11_42") (pintype "unspecified"))
      (node (ref "U3") (pin "36") (pinfunction "DQ11_36") (pintype "bidirectional"))
      (node (ref "U6") (pin "41") (pinfunction "2A1_41") (pintype "unspecified"))
    )
    (net (code "35") (name "FLASH_D28") (class "Default")
      (node (ref "U1") (pin "43") (pinfunction "PE12_43") (pintype "unspecified"))
      (node (ref "U3") (pin "39") (pinfunction "DQ12_39") (pintype "bidirectional"))
      (node (ref "U6") (pin "43") (pinfunction "1A4_43") (pintype "unspecified"))
    )
    (net (code "36") (name "FLASH_D29") (class "Default")
      (node (ref "U1") (pin "44") (pinfunction "PE13_44") (pintype "unspecified"))
      (node (ref "U3") (pin "41") (pinfunction "DQ13_41") (pintype "bidirectional"))
      (node (ref "U6") (pin "44") (pinfunction "1A3_44") (pintype "unspecified"))
    )
    (net (code "37") (name "FLASH_D30") (class "Default")
      (node (ref "U1") (pin "45") (pinfunction "PE14_45") (pintype "unspecified"))
      (node (ref "U3") (pin "43") (pinfunction "DQ14_43") (pintype "bidirectional"))
      (node (ref "U6") (pin "46") (pinfunction "1A2_46") (pintype "unspecified"))
    )
    (net (code "38") (name "FLASH_D31") (class "Default")
      (node (ref "U1") (pin "46") (pinfunction "PE15_46") (pintype "unspecified"))
      (node (ref "U3") (pin "45") (pinfunction "DQ15A-1_45") (pintype "bidirectional"))
      (node (ref "U6") (pin "47") (pinfunction "1A1_47") (pintype "unspecified"))
    )
    (net (code "39") (name "FLASH_OE") (class "Default")
      (node (ref "R7") (pin "2") (pinfunction "2_2") (pintype "input"))
      (node (ref "U1") (pin "52") (pinfunction "PB13_52") (pintype "unspecified"))
      (node (ref "U2") (pin "28") (pinfunction "G_28") (pintype "unspecified"))
      (node (ref "U3") (pin "28") (pinfunction "G_28") (pintype "unspecified"))
    )
    (net (code "40") (name "FLASH_OEWE") (class "Default")
      (node (ref "R13") (pin "1") (pinfunction "1_1") (pintype "input"))
      (node (ref "R2") (pin "2") (pinfunction "2_2") (pintype "input"))
      (node (ref "U1") (pin "96") (pinfunction "PB9_96") (pintype "unspecified"))
    )
    (net (code "41") (name "FLASH_RB") (class "Default")
      (node (ref "U1") (pin "54") (pinfunction "PB15_54") (pintype "unspecified"))
      (node (ref "U2") (pin "15") (pinfunction "RB_15") (pintype "unspecified"))
      (node (ref "U3") (pin "15") (pinfunction "RB_15") (pintype "unspecified"))
    )
    (net (code "42") (name "FLASH_RP") (class "Default")
      (node (ref "R12") (pin "2") (pinfunction "2_2") (pintype "input"))
      (node (ref "U1") (pin "36") (pinfunction "PB1_36") (pintype "unspecified"))
      (node (ref "U2") (pin "12") (pinfunction "RP_12") (pintype "unspecified"))
      (node (ref "U3") (pin "12") (pinfunction "RP_12") (pintype "unspecified"))
    )
    (net (code "43") (name "FLASH_WE") (class "Default")
      (node (ref "Q2") (pin "3") (pinfunction "D_3") (pintype "unspecified"))
      (node (ref "R11") (pin "1") (pinfunction "1_1") (pintype "input"))
      (node (ref "U1") (pin "53") (pinfunction "PB14_53") (pintype "unspecified"))
      (node (ref "U2") (pin "11") (pinfunction "W_11") (pintype "unspecified"))
      (node (ref "U3") (pin "11") (pinfunction "W_11") (pintype "unspecified"))
    )
    (net (code "44") (name "GND") (class "Default")
      (node (ref "C1") (pin "2") (pinfunction "2_2") (pintype "input"))
      (node (ref "C2") (pin "2") (pinfunction "2_2") (pintype "input"))
      (node (ref "C3") (pin "1") (pinfunction "1_1") (pintype "unspecified"))
      (node (ref "C4") (pin "2") (pinfunction "2_2") (pintype "input"))
      (node (ref "C5") (pin "1") (pinfunction "1_1") (pintype "unspecified"))
      (node (ref "C6") (pin "2") (pinfunction "2_2") (pintype "input"))
      (node (ref "C7") (pin "2") (pinfunction "2_2") (pintype "input"))
      (node (ref "C8") (pin "2") (pinfunction "2_2") (pintype "input"))
      (node (ref "H1L") (pin "11") (pinfunction "11_11") (pintype "unspecified"))
      (node (ref "H1R") (pin "11") (pinfunction "11_11") (pintype "unspecified"))
      (node (ref "H3L") (pin "11") (pinfunction "11_11") (pintype "unspecified"))
      (node (ref "H3R") (pin "11") (pinfunction "11_11") (pintype "unspecified"))
      (node (ref "H4") (pin "1") (pinfunction "1_1") (pintype "unspecified"))
      (node (ref "H4L") (pin "11") (pinfunction "11_11") (pintype "unspecified"))
      (node (ref "H5L") (pin "11") (pinfunction "11_11") (pintype "unspecified"))
      (node (ref "H5R") (pin "11") (pinfunction "11_11") (pintype "unspecified"))
      (node (ref "H6") (pin "3") (pinfunction "3_3") (pintype "input"))
      (node (ref "H7L") (pin "11") (pinfunction "11_11") (pintype "unspecified"))
      (node (ref "LED1") (pin "1") (pinfunction "-_1") (pintype "unspecified"))
      (node (ref "LED2") (pin "1") (pinfunction "K_1") (pintype "unspecified"))
      (node (ref "Q2") (pin "2") (pinfunction "S_2") (pintype "unspecified"))
      (node (ref "Q3") (pin "2") (pinfunction "S_2") (pintype "unspecified"))
      (node (ref "R10") (pin "2") (pinfunction "2_2") (pintype "input"))
      (node (ref "R15") (pin "1") (pinfunction "1_1") (pintype "input"))
      (node (ref "R4") (pin "2") (pinfunction "2_2") (pintype "input"))
      (node (ref "R5") (pin "2") (pinfunction "2_2") (pintype "input"))
      (node (ref "R6") (pin "2") (pinfunction "2_2") (pintype "input"))
      (node (ref "U1") (pin "10") (pinfunction "VSS_5_10") (pintype "unspecified"))
      (node (ref "U1") (pin "19") (pinfunction "VSSA_19") (pintype "unspecified"))
      (node (ref "U1") (pin "20") (pinfunction "VREF-_20") (pintype "unspecified"))
      (node (ref "U1") (pin "27") (pinfunction "VSS_4_27") (pintype "unspecified"))
      (node (ref "U1") (pin "37") (pinfunction "PB2_37") (pintype "unspecified"))
      (node (ref "U1") (pin "49") (pinfunction "VSS_1_49") (pintype "unspecified"))
      (node (ref "U1") (pin "74") (pinfunction "VSS_2_74") (pintype "unspecified"))
      (node (ref "U1") (pin "99") (pinfunction "VSS_3_99") (pintype "unspecified"))
      (node (ref "U2") (pin "26") (pinfunction "E_26") (pintype "unspecified"))
      (node (ref "U2") (pin "27") (pinfunction "VSS_27") (pintype "passive"))
      (node (ref "U2") (pin "46") (pinfunction "VSS_46") (pintype "passive"))
      (node (ref "U3") (pin "26") (pinfunction "E_26") (pintype "unspecified"))
      (node (ref "U3") (pin "27") (pinfunction "VSS_27") (pintype "passive"))
      (node (ref "U3") (pin "46") (pinfunction "VSS_46") (pintype "passive"))
      (node (ref "U4") (pin "1") (pinfunction "GND/ADJ_1") (pintype "unspecified"))
      (node (ref "U5") (pin "10") (pinfunction "GND_10") (pintype "unspecified"))
      (node (ref "U5") (pin "15") (pinfunction "GND_15") (pintype "unspecified"))
      (node (ref "U5") (pin "21") (pinfunction "GND_21") (pintype "unspecified"))
      (node (ref "U5") (pin "28") (pinfunction "GND_28") (pintype "unspecified"))
      (node (ref "U5") (pin "34") (pinfunction "GND_34") (pintype "unspecified"))
      (node (ref "U5") (pin "39") (pinfunction "GND_39") (pintype "unspecified"))
      (node (ref "U5") (pin "4") (pinfunction "GND_4") (pintype "unspecified"))
      (node (ref "U5") (pin "45") (pinfunction "GND_45") (pintype "unspecified"))
      (node (ref "U6") (pin "10") (pinfunction "GND_10") (pintype "unspecified"))
      (node (ref "U6") (pin "15") (pinfunction "GND_15") (pintype "unspecified"))
      (node (ref "U6") (pin "21") (pinfunction "GND_21") (pintype "unspecified"))
      (node (ref "U6") (pin "28") (pinfunction "GND_28") (pintype "unspecified"))
      (node (ref "U6") (pin "34") (pinfunction "GND_34") (pintype "unspecified"))
      (node (ref "U6") (pin "39") (pinfunction "GND_39") (pintype "unspecified"))
      (node (ref "U6") (pin "4") (pinfunction "GND_4") (pintype "unspecified"))
      (node (ref "U6") (pin "45") (pinfunction "GND_45") (pintype "unspecified"))
      (node (ref "USBC1") (pin "0") (pinfunction "0_0") (pintype "unspecified"))
      (node (ref "USBC1") (pin "A1B12") (pinfunction "GND_A1B12") (pintype "unspecified"))
      (node (ref "USBC1") (pin "B1A12") (pinfunction "GND_B1A12") (pintype "unspecified"))
    )
    (net (code "45") (name "Net-(LED1-+)") (class "Default")
      (node (ref "LED1") (pin "2") (pinfunction "+_2") (pintype "unspecified"))
      (node (ref "R1") (pin "1") (pinfunction "1_1") (pintype "input"))
    )
    (net (code "46") (name "Net-(LED2-A)") (class "Default")
      (node (ref "LED2") (pin "2") (pinfunction "A_2") (pintype "unspecified"))
      (node (ref "R2") (pin "1") (pinfunction "1_1") (pintype "input"))
    )
    (net (code "47") (name "Net-(LED3--)") (class "Default")
      (node (ref "LED3") (pin "1") (pinfunction "-_1") (pintype "unspecified"))
      (node (ref "R3") (pin "1") (pinfunction "1_1") (pintype "input"))
    )
    (net (code "48") (name "Net-(Q1-D)") (class "Default")
      (node (ref "Q1") (pin "3") (pinfunction "D_3") (pintype "unspecified"))
      (node (ref "R1") (pin "2") (pinfunction "2_2") (pintype "input"))
    )
    (net (code "49") (name "Net-(Q2-G)") (class "Default")
      (node (ref "Q2") (pin "1") (pinfunction "G_1") (pintype "unspecified"))
      (node (ref "Q3") (pin "3") (pinfunction "D_3") (pintype "unspecified"))
      (node (ref "R10") (pin "1") (pinfunction "1_1") (pintype "input"))
      (node (ref "R13") (pin "2") (pinfunction "2_2") (pintype "input"))
    )
    (net (code "50") (name "Net-(U1-OSC_IN)") (class "Default")
      (node (ref "U1") (pin "12") (pinfunction "OSC_IN_12") (pintype "unspecified"))
      (node (ref "X1") (pin "2") (pinfunction "OSC2_2") (pintype "input"))
    )
    (net (code "51") (name "Net-(U1-OSC_OUT)") (class "Default")
      (node (ref "U1") (pin "13") (pinfunction "OSC_OUT_13") (pintype "unspecified"))
      (node (ref "X1") (pin "1") (pinfunction "OSC1_1") (pintype "input"))
    )
    (net (code "52") (name "POWER_LED") (class "Default")
      (node (ref "R3") (pin "2") (pinfunction "2_2") (pintype "input"))
      (node (ref "U1") (pin "95") (pinfunction "PB8_95") (pintype "unspecified"))
    )
    (net (code "53") (name "SENSE_V5") (class "Default")
      (node (ref "R14") (pin "1") (pinfunction "1_1") (pintype "input"))
      (node (ref "R15") (pin "2") (pinfunction "2_2") (pintype "input"))
      (node (ref "U1") (pin "35") (pinfunction "PB0_35") (pintype "unspecified"))
    )
    (net (code "54") (name "SOCKET_A0") (class "Default")
      (node (ref "H1L") (pin "9") (pinfunction "9_9") (pintype "unspecified"))
      (node (ref "H3R") (pin "20") (pinfunction "20_20") (pintype "unspecified"))
      (node (ref "H5R") (pin "20") (pinfunction "20_20") (pintype "unspecified"))
      (node (ref "U1") (pin "15") (pinfunction "PC0_15") (pintype "unspecified"))
      (node (ref "U2") (pin "25") (pinfunction "A0_25") (pintype "unspecified"))
      (node (ref "U3") (pin "25") (pinfunction "A0_25") (pintype "unspecified"))
    )
    (net (code "55") (name "SOCKET_A1") (class "Default")
      (node (ref "H1L") (pin "8") (pinfunction "8_8") (pintype "unspecified"))
      (node (ref "H3R") (pin "19") (pinfunction "19_19") (pintype "unspecified"))
      (node (ref "H5R") (pin "19") (pinfunction "19_19") (pintype "unspecified"))
      (node (ref "U1") (pin "16") (pinfunction "PC1_16") (pintype "unspecified"))
      (node (ref "U2") (pin "24") (pinfunction "A1_24") (pintype "unspecified"))
      (node (ref "U3") (pin "24") (pinfunction "A1_24") (pintype "unspecified"))
    )
    (net (code "56") (name "SOCKET_A2") (class "Default")
      (node (ref "H1L") (pin "7") (pinfunction "7_7") (pintype "unspecified"))
      (node (ref "H3R") (pin "18") (pinfunction "18_18") (pintype "unspecified"))
      (node (ref "H5R") (pin "18") (pinfunction "18_18") (pintype "unspecified"))
      (node (ref "U1") (pin "17") (pinfunction "PC2_17") (pintype "unspecified"))
      (node (ref "U2") (pin "23") (pinfunction "A2_23") (pintype "unspecified"))
      (node (ref "U3") (pin "23") (pinfunction "A2_23") (pintype "unspecified"))
    )
    (net (code "57") (name "SOCKET_A3") (class "Default")
      (node (ref "H1L") (pin "6") (pinfunction "6_6") (pintype "unspecified"))
      (node (ref "H3R") (pin "17") (pinfunction "17_17") (pintype "unspecified"))
      (node (ref "H5R") (pin "17") (pinfunction "17_17") (pintype "unspecified"))
      (node (ref "U1") (pin "18") (pinfunction "PC3_18") (pintype "unspecified"))
      (node (ref "U2") (pin "22") (pinfunction "A3_22") (pintype "unspecified"))
      (node (ref "U3") (pin "22") (pinfunction "A3_22") (pintype "unspecified"))
    )
    (net (code "58") (name "SOCKET_A4") (class "Default")
      (node (ref "H1L") (pin "5") (pinfunction "5_5") (pintype "unspecified"))
      (node (ref "H3R") (pin "16") (pinfunction "16_16") (pintype "unspecified"))
      (node (ref "H5R") (pin "16") (pinfunction "16_16") (pintype "unspecified"))
      (node (ref "U1") (pin "33") (pinfunction "PC4_33") (pintype "unspecified"))
      (node (ref "U2") (pin "21") (pinfunction "A4_21") (pintype "unspecified"))
      (node (ref "U3") (pin "21") (pinfunction "A4_21") (pintype "unspecified"))
    )
    (net (code "59") (name "SOCKET_A5") (class "Default")
      (node (ref "H1L") (pin "4") (pinfunction "4_4") (pintype "unspecified"))
      (node (ref "H3R") (pin "15") (pinfunction "15_15") (pintype "unspecified"))
      (node (ref "H5R") (pin "15") (pinfunction "15_15") (pintype "unspecified"))
      (node (ref "U1") (pin "34") (pinfunction "PC5_34") (pintype "unspecified"))
      (node (ref "U2") (pin "20") (pinfunction "A5_20") (pintype "unspecified"))
      (node (ref "U3") (pin "20") (pinfunction "A5_20") (pintype "unspecified"))
    )
    (net (code "60") (name "SOCKET_A6") (class "Default")
      (node (ref "H1L") (pin "3") (pinfunction "3_3") (pintype "unspecified"))
      (node (ref "H3R") (pin "14") (pinfunction "14_14") (pintype "unspecified"))
      (node (ref "H5R") (pin "14") (pinfunction "14_14") (pintype "unspecified"))
      (node (ref "U1") (pin "63") (pinfunction "PC6_63") (pintype "unspecified"))
      (node (ref "U2") (pin "19") (pinfunction "A6_19") (pintype "unspecified"))
      (node (ref "U3") (pin "19") (pinfunction "A6_19") (pintype "unspecified"))
    )
    (net (code "61") (name "SOCKET_A7") (class "Default")
      (node (ref "H1L") (pin "2") (pinfunction "2_2") (pintype "unspecified"))
      (node (ref "H3R") (pin "13") (pinfunction "13_13") (pintype "unspecified"))
      (node (ref "H5R") (pin "13") (pinfunction "13_13") (pintype "unspecified"))
      (node (ref "U1") (pin "64") (pinfunction "PC7_64") (pintype "unspecified"))
      (node (ref "U2") (pin "18") (pinfunction "A7_18") (pintype "unspecified"))
      (node (ref "U3") (pin "18") (pinfunction "A7_18") (pintype "unspecified"))
    )
    (net (code "62") (name "SOCKET_A8") (class "Default")
      (node (ref "H1R") (pin "1") (pinfunction "1_1") (pintype "unspecified"))
      (node (ref "H3R") (pin "12") (pinfunction "12_12") (pintype "unspecified"))
      (node (ref "H5R") (pin "12") (pinfunction "12_12") (pintype "unspecified"))
      (node (ref "U1") (pin "65") (pinfunction "PC8_65") (pintype "unspecified"))
      (node (ref "U2") (pin "8") (pinfunction "A8_8") (pintype "unspecified"))
      (node (ref "U3") (pin "8") (pinfunction "A8_8") (pintype "unspecified"))
    )
    (net (code "63") (name "SOCKET_A9") (class "Default")
      (node (ref "H1R") (pin "2") (pinfunction "2_2") (pintype "unspecified"))
      (node (ref "H3R") (pin "10") (pinfunction "10_10") (pintype "unspecified"))
      (node (ref "H5R") (pin "10") (pinfunction "10_10") (pintype "unspecified"))
      (node (ref "U1") (pin "66") (pinfunction "PC9_66") (pintype "unspecified"))
      (node (ref "U2") (pin "7") (pinfunction "A9_7") (pintype "unspecified"))
      (node (ref "U3") (pin "7") (pinfunction "A9_7") (pintype "unspecified"))
    )
    (net (code "64") (name "SOCKET_A10") (class "Default")
      (node (ref "H1R") (pin "3") (pinfunction "3_3") (pintype "unspecified"))
      (node (ref "H3R") (pin "9") (pinfunction "9_9") (pintype "unspecified"))
      (node (ref "H5R") (pin "9") (pinfunction "9_9") (pintype "unspecified"))
      (node (ref "U1") (pin "78") (pinfunction "PC10_78") (pintype "unspecified"))
      (node (ref "U2") (pin "6") (pinfunction "A10_6") (pintype "unspecified"))
      (node (ref "U3") (pin "6") (pinfunction "A10_6") (pintype "unspecified"))
    )
    (net (code "65") (name "SOCKET_A11") (class "Default")
      (node (ref "H1R") (pin "4") (pinfunction "4_4") (pintype "unspecified"))
      (node (ref "H3R") (pin "8") (pinfunction "8_8") (pintype "unspecified"))
      (node (ref "H5R") (pin "8") (pinfunction "8_8") (pintype "unspecified"))
      (node (ref "U1") (pin "79") (pinfunction "PC11_79") (pintype "unspecified"))
      (node (ref "U2") (pin "5") (pinfunction "A11_5") (pintype "unspecified"))
      (node (ref "U3") (pin "5") (pinfunction "A11_5") (pintype "unspecified"))
    )
    (net (code "66") (name "SOCKET_A12") (class "Default")
      (node (ref "H1R") (pin "5") (pinfunction "5_5") (pintype "unspecified"))
      (node (ref "H3R") (pin "7") (pinfunction "7_7") (pintype "unspecified"))
      (node (ref "H5R") (pin "7") (pinfunction "7_7") (pintype "unspecified"))
      (node (ref "U1") (pin "80") (pinfunction "PC12_80") (pintype "unspecified"))
      (node (ref "U2") (pin "4") (pinfunction "A12_4") (pintype "unspecified"))
      (node (ref "U3") (pin "4") (pinfunction "A12_4") (pintype "unspecified"))
    )
    (net (code "67") (name "SOCKET_A13") (class "Default")
      (node (ref "H1R") (pin "6") (pinfunction "6_6") (pintype "unspecified"))
      (node (ref "H3R") (pin "6") (pinfunction "6_6") (pintype "unspecified"))
      (node (ref "H5R") (pin "6") (pinfunction "6_6") (pintype "unspecified"))
      (node (ref "U1") (pin "24") (pinfunction "PA1_24") (pintype "unspecified"))
      (node (ref "U1") (pin "7") (pinfunction "PC13-TAMPER-RTC_7") (pintype "unspecified"))
      (node (ref "U2") (pin "3") (pinfunction "A13_3") (pintype "unspecified"))
      (node (ref "U3") (pin "3") (pinfunction "A13_3") (pintype "unspecified"))
    )
    (net (code "68") (name "SOCKET_A14") (class "Default")
      (node (ref "H1R") (pin "7") (pinfunction "7_7") (pintype "unspecified"))
      (node (ref "H3R") (pin "5") (pinfunction "5_5") (pintype "unspecified"))
      (node (ref "H5R") (pin "5") (pinfunction "5_5") (pintype "unspecified"))
      (node (ref "U1") (pin "25") (pinfunction "PA2_25") (pintype "unspecified"))
      (node (ref "U1") (pin "8") (pinfunction "PC14-OSC32_IN_8") (pintype "unspecified"))
      (node (ref "U2") (pin "2") (pinfunction "A14_2") (pintype "unspecified"))
      (node (ref "U3") (pin "2") (pinfunction "A14_2") (pintype "unspecified"))
    )
    (net (code "69") (name "SOCKET_A15") (class "Default")
      (node (ref "H1R") (pin "8") (pinfunction "8_8") (pintype "unspecified"))
      (node (ref "H3R") (pin "4") (pinfunction "4_4") (pintype "unspecified"))
      (node (ref "H5R") (pin "4") (pinfunction "4_4") (pintype "unspecified"))
      (node (ref "U1") (pin "26") (pinfunction "PA3_26") (pintype "unspecified"))
      (node (ref "U1") (pin "9") (pinfunction "PC15-OSC32_OUT_9") (pintype "unspecified"))
      (node (ref "U2") (pin "1") (pinfunction "A15_1") (pintype "unspecified"))
      (node (ref "U3") (pin "1") (pinfunction "A15_1") (pintype "unspecified"))
    )
    (net (code "70") (name "SOCKET_A16") (class "Default")
      (node (ref "H1R") (pin "9") (pinfunction "9_9") (pintype "unspecified"))
      (node (ref "H3R") (pin "3") (pinfunction "3_3") (pintype "unspecified"))
      (node (ref "H5R") (pin "3") (pinfunction "3_3") (pintype "unspecified"))
      (node (ref "U1") (pin "29") (pinfunction "PA4_29") (pintype "unspecified"))
      (node (ref "U2") (pin "48") (pinfunction "A16_48") (pintype "unspecified"))
      (node (ref "U3") (pin "48") (pinfunction "A16_48") (pintype "unspecified"))
    )
    (net (code "71") (name "SOCKET_A17") (class "Default")
      (node (ref "H1L") (pin "1") (pinfunction "1_1") (pintype "unspecified"))
      (node (ref "H3R") (pin "2") (pinfunction "2_2") (pintype "unspecified"))
      (node (ref "H9") (pin "1") (pinfunction "1_1") (pintype "input"))
      (node (ref "R16") (pin "1") (pinfunction "1_1") (pintype "input"))
    )
    (net (code "72") (name "SOCKET_A18") (class "Default")
      (node (ref "H7") (pin "1") (pinfunction "1_1") (pintype "unspecified"))
      (node (ref "R9") (pin "1") (pinfunction "1_1") (pintype "input"))
      (node (ref "U1") (pin "31") (pinfunction "PA6_31") (pintype "unspecified"))
    )
    (net (code "73") (name "SOCKET_A19") (class "Default")
      (node (ref "H8") (pin "1") (pinfunction "1_1") (pintype "unspecified"))
      (node (ref "R8") (pin "1") (pinfunction "1_1") (pintype "input"))
      (node (ref "U1") (pin "32") (pinfunction "PA7_32") (pintype "unspecified"))
    )
    (net (code "74") (name "SOCKET_D0") (class "Default")
      (node (ref "H1L") (pin "13") (pinfunction "13_13") (pintype "unspecified"))
      (node (ref "H3L") (pin "19") (pinfunction "19_19") (pintype "unspecified"))
      (node (ref "H7L") (pin "19") (pinfunction "19_19") (pintype "unspecified"))
      (node (ref "U5") (pin "23") (pinfunction "4Y4_23") (pintype "unspecified"))
    )
    (net (code "75") (name "SOCKET_D1") (class "Default")
      (node (ref "H1L") (pin "15") (pinfunction "15_15") (pintype "unspecified"))
      (node (ref "H3L") (pin "18") (pinfunction "18_18") (pintype "unspecified"))
      (node (ref "H7L") (pin "18") (pinfunction "18_18") (pintype "unspecified"))
      (node (ref "U5") (pin "22") (pinfunction "4Y3_22") (pintype "unspecified"))
    )
    (net (code "76") (name "SOCKET_D2") (class "Default")
      (node (ref "H1L") (pin "17") (pinfunction "17_17") (pintype "unspecified"))
      (node (ref "H3L") (pin "17") (pinfunction "17_17") (pintype "unspecified"))
      (node (ref "H7L") (pin "17") (pinfunction "17_17") (pintype "unspecified"))
      (node (ref "U5") (pin "20") (pinfunction "4Y2_20") (pintype "unspecified"))
    )
    (net (code "77") (name "SOCKET_D3") (class "Default")
      (node (ref "H1L") (pin "19") (pinfunction "19_19") (pintype "unspecified"))
      (node (ref "H3L") (pin "16") (pinfunction "16_16") (pintype "unspecified"))
      (node (ref "H7L") (pin "16") (pinfunction "16_16") (pintype "unspecified"))
      (node (ref "U5") (pin "19") (pinfunction "4Y1_19") (pintype "unspecified"))
    )
    (net (code "78") (name "SOCKET_D4") (class "Default")
      (node (ref "H1R") (pin "19") (pinfunction "19_19") (pintype "unspecified"))
      (node (ref "H3L") (pin "15") (pinfunction "15_15") (pintype "unspecified"))
      (node (ref "H7L") (pin "15") (pinfunction "15_15") (pintype "unspecified"))
      (node (ref "U5") (pin "17") (pinfunction "3Y4_17") (pintype "unspecified"))
    )
    (net (code "79") (name "SOCKET_D5") (class "Default")
      (node (ref "H1R") (pin "17") (pinfunction "17_17") (pintype "unspecified"))
      (node (ref "H3L") (pin "14") (pinfunction "14_14") (pintype "unspecified"))
      (node (ref "H7L") (pin "14") (pinfunction "14_14") (pintype "unspecified"))
      (node (ref "U5") (pin "16") (pinfunction "3Y3_16") (pintype "unspecified"))
    )
    (net (code "80") (name "SOCKET_D6") (class "Default")
      (node (ref "H1R") (pin "15") (pinfunction "15_15") (pintype "unspecified"))
      (node (ref "H3L") (pin "13") (pinfunction "13_13") (pintype "unspecified"))
      (node (ref "H7L") (pin "13") (pinfunction "13_13") (pintype "unspecified"))
      (node (ref "U5") (pin "14") (pinfunction "3Y2_14") (pintype "unspecified"))
    )
    (net (code "81") (name "SOCKET_D7") (class "Default")
      (node (ref "H1R") (pin "13") (pinfunction "13_13") (pintype "unspecified"))
      (node (ref "H3L") (pin "12") (pinfunction "12_12") (pintype "unspecified"))
      (node (ref "H7L") (pin "12") (pinfunction "12_12") (pintype "unspecified"))
      (node (ref "U5") (pin "13") (pinfunction "3Y1_13") (pintype "unspecified"))
    )
    (net (code "82") (name "SOCKET_D8") (class "Default")
      (node (ref "H1L") (pin "14") (pinfunction "14_14") (pintype "unspecified"))
      (node (ref "H3L") (pin "10") (pinfunction "10_10") (pintype "unspecified"))
      (node (ref "H7L") (pin "10") (pinfunction "10_10") (pintype "unspecified"))
      (node (ref "U5") (pin "12") (pinfunction "2Y4_12") (pintype "unspecified"))
    )
    (net (code "83") (name "SOCKET_D9") (class "Default")
      (node (ref "H1L") (pin "16") (pinfunction "16_16") (pintype "unspecified"))
      (node (ref "H3L") (pin "9") (pinfunction "9_9") (pintype "unspecified"))
      (node (ref "H7L") (pin "9") (pinfunction "9_9") (pintype "unspecified"))
      (node (ref "U5") (pin "11") (pinfunction "2Y3_11") (pintype "unspecified"))
    )
    (net (code "84") (name "SOCKET_D10") (class "Default")
      (node (ref "H1L") (pin "18") (pinfunction "18_18") (pintype "unspecified"))
      (node (ref "H3L") (pin "8") (pinfunction "8_8") (pintype "unspecified"))
      (node (ref "H7L") (pin "8") (pinfunction "8_8") (pintype "unspecified"))
      (node (ref "U5") (pin "9") (pinfunction "2Y2_9") (pintype "unspecified"))
    )
    (net (code "85") (name "SOCKET_D11") (class "Default")
      (node (ref "H1L") (pin "20") (pinfunction "20_20") (pintype "unspecified"))
      (node (ref "H3L") (pin "7") (pinfunction "7_7") (pintype "unspecified"))
      (node (ref "H7L") (pin "7") (pinfunction "7_7") (pintype "unspecified"))
      (node (ref "U5") (pin "8") (pinfunction "2Y1_8") (pintype "unspecified"))
    )
    (net (code "86") (name "SOCKET_D12") (class "Default")
      (node (ref "H1R") (pin "18") (pinfunction "18_18") (pintype "unspecified"))
      (node (ref "H3L") (pin "6") (pinfunction "6_6") (pintype "unspecified"))
      (node (ref "H7L") (pin "6") (pinfunction "6_6") (pintype "unspecified"))
      (node (ref "U5") (pin "6") (pinfunction "1Y4_6") (pintype "unspecified"))
    )
    (net (code "87") (name "SOCKET_D13") (class "Default")
      (node (ref "H1R") (pin "16") (pinfunction "16_16") (pintype "unspecified"))
      (node (ref "H3L") (pin "5") (pinfunction "5_5") (pintype "unspecified"))
      (node (ref "H7L") (pin "5") (pinfunction "5_5") (pintype "unspecified"))
      (node (ref "U5") (pin "5") (pinfunction "1Y3_5") (pintype "unspecified"))
    )
    (net (code "88") (name "SOCKET_D14") (class "Default")
      (node (ref "H1R") (pin "14") (pinfunction "14_14") (pintype "unspecified"))
      (node (ref "H3L") (pin "4") (pinfunction "4_4") (pintype "unspecified"))
      (node (ref "H7L") (pin "4") (pinfunction "4_4") (pintype "unspecified"))
      (node (ref "U5") (pin "3") (pinfunction "1Y2_3") (pintype "unspecified"))
    )
    (net (code "89") (name "SOCKET_D15") (class "Default")
      (node (ref "H1R") (pin "12") (pinfunction "12_12") (pintype "unspecified"))
      (node (ref "H3L") (pin "3") (pinfunction "3_3") (pintype "unspecified"))
      (node (ref "H7L") (pin "3") (pinfunction "3_3") (pintype "unspecified"))
      (node (ref "U5") (pin "2") (pinfunction "1Y1_2") (pintype "unspecified"))
    )
    (net (code "90") (name "SOCKET_D16") (class "Default")
      (node (ref "H2L") (pin "2") (pinfunction "2_2") (pintype "unspecified"))
      (node (ref "H4L") (pin "19") (pinfunction "19_19") (pintype "unspecified"))
      (node (ref "H5L") (pin "19") (pinfunction "19_19") (pintype "unspecified"))
      (node (ref "U6") (pin "23") (pinfunction "4Y4_23") (pintype "unspecified"))
    )
    (net (code "91") (name "SOCKET_D17") (class "Default")
      (node (ref "H2L") (pin "4") (pinfunction "4_4") (pintype "unspecified"))
      (node (ref "H4L") (pin "18") (pinfunction "18_18") (pintype "unspecified"))
      (node (ref "H5L") (pin "18") (pinfunction "18_18") (pintype "unspecified"))
      (node (ref "U6") (pin "22") (pinfunction "4Y3_22") (pintype "unspecified"))
    )
    (net (code "92") (name "SOCKET_D18") (class "Default")
      (node (ref "H2L") (pin "6") (pinfunction "6_6") (pintype "unspecified"))
      (node (ref "H4L") (pin "17") (pinfunction "17_17") (pintype "unspecified"))
      (node (ref "H5L") (pin "17") (pinfunction "17_17") (pintype "unspecified"))
      (node (ref "U6") (pin "20") (pinfunction "4Y2_20") (pintype "unspecified"))
    )
    (net (code "93") (name "SOCKET_D19") (class "Default")
      (node (ref "H2L") (pin "8") (pinfunction "8_8") (pintype "unspecified"))
      (node (ref "H4L") (pin "16") (pinfunction "16_16") (pintype "unspecified"))
      (node (ref "H5L") (pin "16") (pinfunction "16_16") (pintype "unspecified"))
      (node (ref "U6") (pin "19") (pinfunction "4Y1_19") (pintype "unspecified"))
    )
    (net (code "94") (name "SOCKET_D20") (class "Default")
      (node (ref "H2R") (pin "8") (pinfunction "8_8") (pintype "unspecified"))
      (node (ref "H4L") (pin "15") (pinfunction "15_15") (pintype "unspecified"))
      (node (ref "H5L") (pin "15") (pinfunction "15_15") (pintype "unspecified"))
      (node (ref "U6") (pin "17") (pinfunction "3Y4_17") (pintype "unspecified"))
    )
    (net (code "95") (name "SOCKET_D21") (class "Default")
      (node (ref "H2R") (pin "6") (pinfunction "6_6") (pintype "unspecified"))
      (node (ref "H4L") (pin "14") (pinfunction "14_14") (pintype "unspecified"))
      (node (ref "H5L") (pin "14") (pinfunction "14_14") (pintype "unspecified"))
      (node (ref "U6") (pin "16") (pinfunction "3Y3_16") (pintype "unspecified"))
    )
    (net (code "96") (name "SOCKET_D22") (class "Default")
      (node (ref "H2R") (pin "4") (pinfunction "4_4") (pintype "unspecified"))
      (node (ref "H4L") (pin "13") (pinfunction "13_13") (pintype "unspecified"))
      (node (ref "H5L") (pin "13") (pinfunction "13_13") (pintype "unspecified"))
      (node (ref "U6") (pin "14") (pinfunction "3Y2_14") (pintype "unspecified"))
    )
    (net (code "97") (name "SOCKET_D23") (class "Default")
      (node (ref "H2R") (pin "2") (pinfunction "2_2") (pintype "unspecified"))
      (node (ref "H4L") (pin "12") (pinfunction "12_12") (pintype "unspecified"))
      (node (ref "H5L") (pin "12") (pinfunction "12_12") (pintype "unspecified"))
      (node (ref "U6") (pin "13") (pinfunction "3Y1_13") (pintype "unspecified"))
    )
    (net (code "98") (name "SOCKET_D24") (class "Default")
      (node (ref "H2L") (pin "3") (pinfunction "3_3") (pintype "unspecified"))
      (node (ref "H4L") (pin "10") (pinfunction "10_10") (pintype "unspecified"))
      (node (ref "H5L") (pin "10") (pinfunction "10_10") (pintype "unspecified"))
      (node (ref "U6") (pin "12") (pinfunction "2Y4_12") (pintype "unspecified"))
    )
    (net (code "99") (name "SOCKET_D25") (class "Default")
      (node (ref "H2L") (pin "5") (pinfunction "5_5") (pintype "unspecified"))
      (node (ref "H4L") (pin "9") (pinfunction "9_9") (pintype "unspecified"))
      (node (ref "H5L") (pin "9") (pinfunction "9_9") (pintype "unspecified"))
      (node (ref "U6") (pin "11") (pinfunction "2Y3_11") (pintype "unspecified"))
    )
    (net (code "100") (name "SOCKET_D26") (class "Default")
      (node (ref "H2L") (pin "7") (pinfunction "7_7") (pintype "unspecified"))
      (node (ref "H4L") (pin "8") (pinfunction "8_8") (pintype "unspecified"))
      (node (ref "H5L") (pin "8") (pinfunction "8_8") (pintype "unspecified"))
      (node (ref "U6") (pin "9") (pinfunction "2Y2_9") (pintype "unspecified"))
    )
    (net (code "101") (name "SOCKET_D27") (class "Default")
      (node (ref "H2L") (pin "9") (pinfunction "9_9") (pintype "unspecified"))
      (node (ref "H4L") (pin "7") (pinfunction "7_7") (pintype "unspecified"))
      (node (ref "H5L") (pin "7") (pinfunction "7_7") (pintype "unspecified"))
      (node (ref "U6") (pin "8") (pinfunction "2Y1_8") (pintype "unspecified"))
    )
    (net (code "102") (name "SOCKET_D28") (class "Default")
      (node (ref "H2R") (pin "7") (pinfunction "7_7") (pintype "unspecified"))
      (node (ref "H4L") (pin "6") (pinfunction "6_6") (pintype "unspecified"))
      (node (ref "H5L") (pin "6") (pinfunction "6_6") (pintype "unspecified"))
      (node (ref "U6") (pin "6") (pinfunction "1Y4_6") (pintype "unspecified"))
    )
    (net (code "103") (name "SOCKET_D29") (class "Default")
      (node (ref "H2R") (pin "5") (pinfunction "5_5") (pintype "unspecified"))
      (node (ref "H4L") (pin "5") (pinfunction "5_5") (pintype "unspecified"))
      (node (ref "H5L") (pin "5") (pinfunction "5_5") (pintype "unspecified"))
      (node (ref "U6") (pin "5") (pinfunction "1Y3_5") (pintype "unspecified"))
    )
    (net (code "104") (name "SOCKET_D30") (class "Default")
      (node (ref "H2R") (pin "3") (pinfunction "3_3") (pintype "unspecified"))
      (node (ref "H4L") (pin "4") (pinfunction "4_4") (pintype "unspecified"))
      (node (ref "H5L") (pin "4") (pinfunction "4_4") (pintype "unspecified"))
      (node (ref "U6") (pin "3") (pinfunction "1Y2_3") (pintype "unspecified"))
    )
    (net (code "105") (name "SOCKET_D31") (class "Default")
      (node (ref "H2R") (pin "1") (pinfunction "1_1") (pintype "unspecified"))
      (node (ref "H4L") (pin "3") (pinfunction "3_3") (pintype "unspecified"))
      (node (ref "H5L") (pin "3") (pinfunction "3_3") (pintype "unspecified"))
      (node (ref "U1") (pin "51") (pinfunction "PB12_51") (pintype "unspecified"))
      (node (ref "U6") (pin "2") (pinfunction "1Y1_2") (pintype "unspecified"))
    )
    (net (code "106") (name "SOCKET_OE") (class "Default")
      (node (ref "H1L") (pin "12") (pinfunction "12_12") (pintype "unspecified"))
      (node (ref "H2L") (pin "1") (pinfunction "1_1") (pintype "unspecified"))
      (node (ref "H3L") (pin "20") (pinfunction "20_20") (pintype "unspecified"))
      (node (ref "H4L") (pin "20") (pinfunction "20_20") (pintype "unspecified"))
      (node (ref "H5L") (pin "20") (pinfunction "20_20") (pintype "unspecified"))
      (node (ref "H7L") (pin "20") (pinfunction "20_20") (pintype "unspecified"))
      (node (ref "Q1") (pin "1") (pinfunction "G_1") (pintype "unspecified"))
      (node (ref "Q3") (pin "1") (pinfunction "G_1") (pintype "unspecified"))
      (node (ref "R7") (pin "1") (pinfunction "1_1") (pintype "input"))
      (node (ref "U1") (pin "23") (pinfunction "PA0-WKUP_23") (pintype "unspecified"))
      (node (ref "U5") (pin "1") (pinfunction "1OE#_1") (pintype "unspecified"))
      (node (ref "U5") (pin "24") (pinfunction "4OE#_24") (pintype "unspecified"))
      (node (ref "U5") (pin "25") (pinfunction "3OE#_25") (pintype "unspecified"))
      (node (ref "U5") (pin "48") (pinfunction "2OE#_48") (pintype "unspecified"))
      (node (ref "U6") (pin "1") (pinfunction "1OE#_1") (pintype "unspecified"))
      (node (ref "U6") (pin "24") (pinfunction "4OE#_24") (pintype "unspecified"))
      (node (ref "U6") (pin "25") (pinfunction "3OE#_25") (pintype "unspecified"))
      (node (ref "U6") (pin "48") (pinfunction "2OE#_48") (pintype "unspecified"))
    )
    (net (code "107") (name "SOCKET_V5") (class "Default")
      (node (ref "D2") (pin "2") (pinfunction "+_2") (pintype "unspecified"))
      (node (ref "H1R") (pin "20") (pinfunction "20_20") (pintype "unspecified"))
      (node (ref "H2R") (pin "9") (pinfunction "9_9") (pintype "unspecified"))
      (node (ref "H3R") (pin "1") (pinfunction "1_1") (pintype "unspecified"))
      (node (ref "H5R") (pin "1") (pinfunction "1_1") (pintype "unspecified"))
      (node (ref "R14") (pin "2") (pinfunction "2_2") (pintype "input"))
    )
    (net (code "108") (name "STM_BOOT0") (class "Default")
      (node (ref "H5") (pin "1") (pinfunction "1_1") (pintype "unspecified"))
      (node (ref "R6") (pin "1") (pinfunction "1_1") (pintype "input"))
      (node (ref "U1") (pin "91") (pinfunction "PB5_91") (pintype "unspecified"))
      (node (ref "U1") (pin "94") (pinfunction "BOOT0_94") (pintype "unspecified"))
    )
    (net (code "109") (name "STM_NRST") (class "Default")
      (node (ref "H6") (pin "5") (pinfunction "5_5") (pintype "input"))
      (node (ref "U1") (pin "14") (pinfunction "NRST_14") (pintype "unspecified"))
    )
    (net (code "110") (name "STM_SWCLK_TCK") (class "Default")
      (node (ref "H6") (pin "2") (pinfunction "2_2") (pintype "input"))
      (node (ref "U1") (pin "76") (pinfunction "PA14_76") (pintype "unspecified"))
    )
    (net (code "111") (name "STM_SWDIO_TMS") (class "Default")
      (node (ref "H6") (pin "4") (pinfunction "4_4") (pintype "input"))
      (node (ref "U1") (pin "72") (pinfunction "PA13_72") (pintype "unspecified"))
    )
    (net (code "112") (name "STM_SWO_TDO") (class "Default")
      (node (ref "H6") (pin "6") (pinfunction "6_6") (pintype "input"))
      (node (ref "U1") (pin "89") (pinfunction "PB3_89") (pintype "unspecified"))
    )
    (net (code "113") (name "USB_CC1") (class "Default")
      (node (ref "R5") (pin "1") (pinfunction "1_1") (pintype "input"))
      (node (ref "U1") (pin "67") (pinfunction "PA8_67") (pintype "unspecified"))
      (node (ref "USBC1") (pin "A5") (pinfunction "CC1_A5") (pintype "unspecified"))
    )
    (net (code "114") (name "USB_CC2") (class "Default")
      (node (ref "R4") (pin "1") (pinfunction "1_1") (pintype "input"))
      (node (ref "U1") (pin "69") (pinfunction "PA10_69") (pintype "unspecified"))
      (node (ref "USBC1") (pin "B5") (pinfunction "CC2_B5") (pintype "unspecified"))
    )
    (net (code "115") (name "USB_DM") (class "Default")
      (node (ref "U1") (pin "70") (pinfunction "PA11_70") (pintype "unspecified"))
      (node (ref "USBC1") (pin "A7") (pinfunction "DN1_A7") (pintype "unspecified"))
      (node (ref "USBC1") (pin "B7") (pinfunction "DN2_B7") (pintype "unspecified"))
    )
    (net (code "116") (name "USB_DP") (class "Default")
      (node (ref "U1") (pin "71") (pinfunction "PA12_71") (pintype "unspecified"))
      (node (ref "USBC1") (pin "A6") (pinfunction "DP1_A6") (pintype "unspecified"))
      (node (ref "USBC1") (pin "B6") (pinfunction "DP2_B6") (pintype "unspecified"))
    )
    (net (code "117") (name "USB_V5") (class "Default")
      (node (ref "D1") (pin "2") (pinfunction "+_2") (pintype "unspecified"))
      (node (ref "U1") (pin "68") (pinfunction "PA9_68") (pintype "unspecified"))
      (node (ref "USBC1") (pin "A4B9") (pinfunction "VBUS_A4B9") (pintype "unspecified"))
      (node (ref "USBC1") (pin "B4A9") (pinfunction "VBUS_B4A9") (pintype "unspecified"))
    )
    (net (code "118") (name "V3P3") (class "Default")
      (node (ref "C4") (pin "1") (pinfunction "1_1") (pintype "input"))
      (node (ref "C5") (pin "2") (pinfunction "2_2") (pintype "unspecified"))
      (node (ref "C6") (pin "1") (pinfunction "1_1") (pintype "input"))
      (node (ref "C7") (pin "1") (pinfunction "1_1") (pintype "input"))
      (node (ref "C8") (pin "1") (pinfunction "1_1") (pintype "input"))
      (node (ref "H6") (pin "1") (pinfunction "1_1") (pintype "input"))
      (node (ref "U1") (pin "100") (pinfunction "VDD_3_100") (pintype "unspecified"))
      (node (ref "U1") (pin "11") (pinfunction "VDD_5_11") (pintype "unspecified"))
      (node (ref "U1") (pin "21") (pinfunction "VREF+_21") (pintype "unspecified"))
      (node (ref "U1") (pin "22") (pinfunction "VDDA_22") (pintype "unspecified"))
      (node (ref "U1") (pin "28") (pinfunction "VDD_4_28") (pintype "unspecified"))
      (node (ref "U1") (pin "50") (pinfunction "VDD_1_50") (pintype "unspecified"))
      (node (ref "U1") (pin "6") (pinfunction "VBAT_6") (pintype "unspecified"))
      (node (ref "U1") (pin "75") (pinfunction "VDD_2_75") (pintype "unspecified"))
      (node (ref "U4") (pin "2") (pinfunction "Vout_2") (pintype "unspecified"))
      (node (ref "U4") (pin "4") (pinfunction "Vout_4") (pintype "unspecified"))
    )
    (net (code "119") (name "V5") (class "Default")
      (node (ref "C1") (pin "1") (pinfunction "1_1") (pintype "input"))
      (node (ref "C2") (pin "1") (pinfunction "1_1") (pintype "input"))
      (node (ref "C3") (pin "2") (pinfunction "2_2") (pintype "unspecified"))
      (node (ref "D1") (pin "1") (pinfunction "-_1") (pintype "unspecified"))
      (node (ref "D2") (pin "1") (pinfunction "-_1") (pintype "unspecified"))
      (node (ref "LED3") (pin "2") (pinfunction "+_2") (pintype "unspecified"))
      (node (ref "Q1") (pin "2") (pinfunction "S_2") (pintype "unspecified"))
      (node (ref "R11") (pin "2") (pinfunction "2_2") (pintype "input"))
      (node (ref "R12") (pin "1") (pinfunction "1_1") (pintype "input"))
      (node (ref "U2") (pin "37") (pinfunction "VCC_37") (pintype "passive"))
      (node (ref "U2") (pin "47") (pinfunction "BYTE_47") (pintype "unspecified"))
      (node (ref "U3") (pin "37") (pinfunction "VCC_37") (pintype "passive"))
      (node (ref "U3") (pin "47") (pinfunction "BYTE_47") (pintype "unspecified"))
      (node (ref "U4") (pin "3") (pinfunction "Vin_3") (pintype "unspecified"))
      (node (ref "U5") (pin "18") (pinfunction "VCC_18") (pintype "unspecified"))
      (node (ref "U5") (pin "31") (pinfunction "VCC_31") (pintype "unspecified"))
      (node (ref "U5") (pin "42") (pinfunction "VCC_42") (pintype "unspecified"))
      (node (ref "U5") (pin "7") (pinfunction "VCC_7") (pintype "unspecified"))
      (node (ref "U6") (pin "18") (pinfunction "VCC_18") (pintype "unspecified"))
      (node (ref "U6") (pin "31") (pinfunction "VCC_31") (pintype "unspecified"))
      (node (ref "U6") (pin "42") (pinfunction "VCC_42") (pintype "unspecified"))
      (node (ref "U6") (pin "7") (pinfunction "VCC_7") (pintype "unspecified"))
    )
    (net (code "120") (name "unconnected-(H1L-Pad10)") (class "Default")
      (node (ref "H1L") (pin "10") (pinfunction "10_10") (pintype "unspecified+no_connect"))
    )
    (net (code "121") (name "unconnected-(H1R-Pad10)") (class "Default")
      (node (ref "H1R") (pin "10") (pinfunction "10_10") (pintype "unspecified+no_connect"))
    )
    (net (code "122") (name "unconnected-(H3L-Pad1)") (class "Default")
      (node (ref "H3L") (pin "1") (pinfunction "1_1") (pintype "unspecified+no_connect"))
    )
    (net (code "123") (name "unconnected-(H3L-Pad2)") (class "Default")
      (node (ref "H3L") (pin "2") (pinfunction "2_2") (pintype "unspecified+no_connect"))
    )
    (net (code "124") (name "unconnected-(H4L-Pad1)") (class "Default")
      (node (ref "H4L") (pin "1") (pinfunction "1_1") (pintype "unspecified+no_connect"))
    )
    (net (code "125") (name "unconnected-(H4L-Pad2)") (class "Default")
      (node (ref "H4L") (pin "2") (pinfunction "2_2") (pintype "unspecified+no_connect"))
    )
    (net (code "126") (name "unconnected-(H5L-Pad1)") (class "Default")
      (node (ref "H5L") (pin "1") (pinfunction "1_1") (pintype "unspecified+no_connect"))
    )
    (net (code "127") (name "unconnected-(H5L-Pad2)") (class "Default")
      (node (ref "H5L") (pin "2") (pinfunction "2_2") (pintype "unspecified+no_connect"))
    )
    (net (code "128") (name "unconnected-(H5R-Pad2)") (class "Default")
      (node (ref "H5R") (pin "2") (pinfunction "2_2") (pintype "unspecified+no_connect"))
    )
    (net (code "129") (name "unconnected-(H7L-Pad1)") (class "Default")
      (node (ref "H7L") (pin "1") (pinfunction "1_1") (pintype "unspecified+no_connect"))
    )
    (net (code "130") (name "unconnected-(H7L-Pad2)") (class "Default")
      (node (ref "H7L") (pin "2") (pinfunction "2_2") (pintype "unspecified+no_connect"))
    )
    (net (code "131") (name "unconnected-(U1-NC-Pad73)") (class "Default")
      (node (ref "U1") (pin "73") (pinfunction "NC_73") (pintype "unspecified+no_connect"))
    )
    (net (code "132") (name "unconnected-(U1-PA15-Pad77)") (class "Default")
      (node (ref "U1") (pin "77") (pinfunction "PA15_77") (pintype "unspecified+no_connect"))
    )
    (net (code "133") (name "unconnected-(U2-NC-Pad10)") (class "Default")
      (node (ref "U2") (pin "10") (pinfunction "NC_10") (pintype "unspecified+no_connect"))
    )
    (net (code "134") (name "unconnected-(U2-NC-Pad13)") (class "Default")
      (node (ref "U2") (pin "13") (pinfunction "NC_13") (pintype "unspecified+no_connect"))
    )
    (net (code "135") (name "unconnected-(U2-NC-Pad14)") (class "Default")
      (node (ref "U2") (pin "14") (pinfunction "NC_14") (pintype "unspecified+no_connect"))
    )
    (net (code "136") (name "unconnected-(U3-NC-Pad10)") (class "Default")
      (node (ref "U3") (pin "10") (pinfunction "NC_10") (pintype "unspecified+no_connect"))
    )
    (net (code "137") (name "unconnected-(U3-NC-Pad13)") (class "Default")
      (node (ref "U3") (pin "13") (pinfunction "NC_13") (pintype "unspecified+no_connect"))
    )
    (net (code "138") (name "unconnected-(U3-NC-Pad14)") (class "Default")
      (node (ref "U3") (pin "14") (pinfunction "NC_14") (pintype "unspecified+no_connect"))
    )
    (net (code "139") (name "unconnected-(USBC1-SBU1-PadA8)") (class "Default")
      (node (ref "USBC1") (pin "A8") (pinfunction "SBU1_A8") (pintype "unspecified+no_connect"))
    )
    (net (code "140") (name "unconnected-(USBC1-SBU2-PadB8)") (class "Default")
      (node (ref "USBC1") (pin "B8") (pinfunction "SBU2_B8") (pintype "unspecified+no_connect"))
    )
  )
)
